# Main.net
KiCad netlist of a schematic drawn in EAGLE
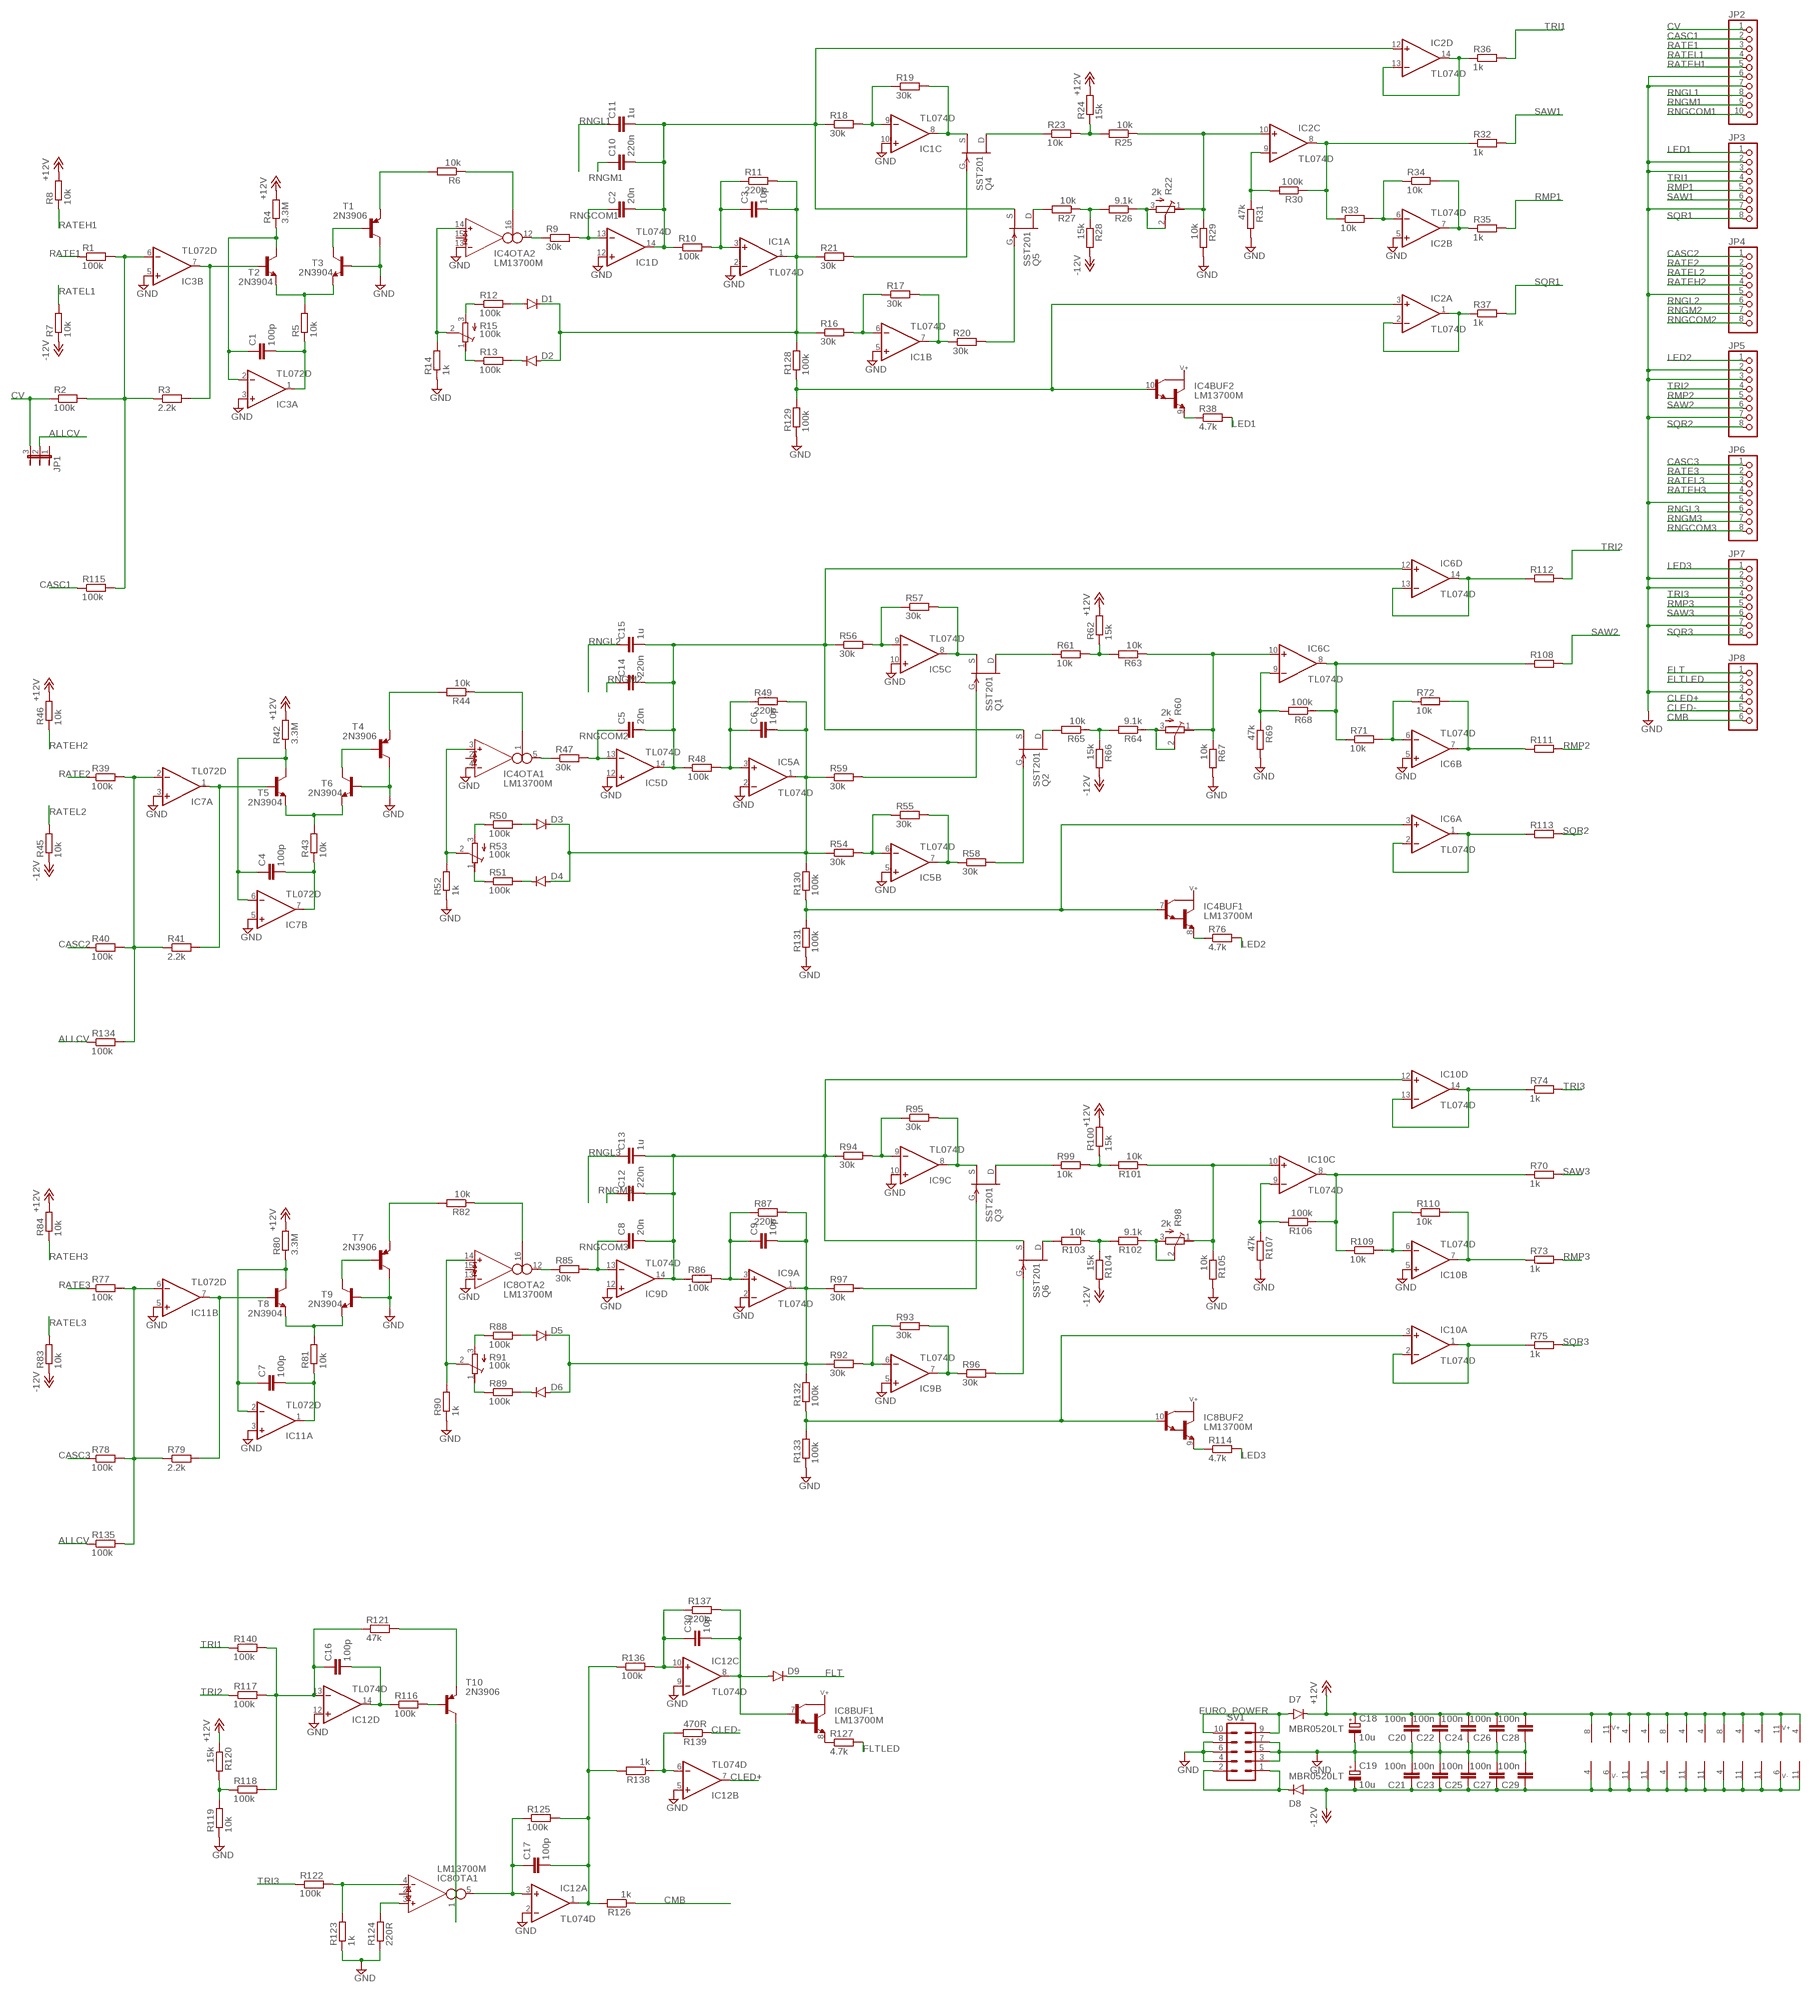
[diagram p0: schematic, sheet 1]

(export (version "E")
  (design (tool "Eeschema 10.0.6"))
  (components
    (comp (ref "C1")
      (value "100p")
      (footprint "eagle-import:C0805")
      (libsource (lib "eagle-import") (part "C-EUC0805"))
    )
    (comp (ref "C2")
      (value "20n")
      (footprint "eagle-import:C050-025X075")
      (libsource (lib "eagle-import") (part "C-EU050-025X075"))
    )
    (comp (ref "C3")
      (value "10p")
      (footprint "eagle-import:C0805")
      (libsource (lib "eagle-import") (part "C-EUC0805"))
    )
    (comp (ref "C4")
      (value "100p")
      (footprint "eagle-import:C0805")
      (libsource (lib "eagle-import") (part "C-EUC0805"))
    )
    (comp (ref "C5")
      (value "20n")
      (footprint "eagle-import:C050-025X075")
      (libsource (lib "eagle-import") (part "C-EU050-025X075"))
    )
    (comp (ref "C6")
      (value "10p")
      (footprint "eagle-import:C0805")
      (libsource (lib "eagle-import") (part "C-EUC0805"))
    )
    (comp (ref "C7")
      (value "100p")
      (footprint "eagle-import:C0805")
      (libsource (lib "eagle-import") (part "C-EUC0805"))
    )
    (comp (ref "C8")
      (value "20n")
      (footprint "eagle-import:C050-025X075")
      (libsource (lib "eagle-import") (part "C-EU050-025X075"))
    )
    (comp (ref "C9")
      (value "10p")
      (footprint "eagle-import:C0805")
      (libsource (lib "eagle-import") (part "C-EUC0805"))
    )
    (comp (ref "C10")
      (value "220n")
      (footprint "eagle-import:C050-035X075")
      (libsource (lib "eagle-import") (part "C-EU050-035X075"))
    )
    (comp (ref "C11")
      (value "1u")
      (footprint "eagle-import:C050-045X075")
      (libsource (lib "eagle-import") (part "C-EU050-045X075"))
    )
    (comp (ref "C12")
      (value "220n")
      (footprint "eagle-import:C050-035X075")
      (libsource (lib "eagle-import") (part "C-EU050-035X075"))
    )
    (comp (ref "C13")
      (value "1u")
      (footprint "eagle-import:C050-045X075")
      (libsource (lib "eagle-import") (part "C-EU050-045X075"))
    )
    (comp (ref "C14")
      (value "220n")
      (footprint "eagle-import:C050-035X075")
      (libsource (lib "eagle-import") (part "C-EU050-035X075"))
    )
    (comp (ref "C15")
      (value "1u")
      (footprint "eagle-import:C050-045X075")
      (libsource (lib "eagle-import") (part "C-EU050-045X075"))
    )
    (comp (ref "C16")
      (value "100p")
      (footprint "eagle-import:C0805")
      (libsource (lib "eagle-import") (part "C-EUC0805"))
    )
    (comp (ref "C17")
      (value "100p")
      (footprint "eagle-import:C0805")
      (libsource (lib "eagle-import") (part "C-EUC0805"))
    )
    (comp (ref "C18")
      (value "10u")
      (footprint "eagle-import:E2,5-5")
      (libsource (lib "eagle-import") (part "CPOL-EUE2.5-5"))
    )
    (comp (ref "C19")
      (value "10u")
      (footprint "eagle-import:E2,5-5")
      (libsource (lib "eagle-import") (part "CPOL-EUE2.5-5"))
    )
    (comp (ref "C20")
      (value "100n")
      (footprint "eagle-import:C0805")
      (libsource (lib "eagle-import") (part "C-EUC0805"))
    )
    (comp (ref "C21")
      (value "100n")
      (footprint "eagle-import:C0805")
      (libsource (lib "eagle-import") (part "C-EUC0805"))
    )
    (comp (ref "C22")
      (value "100n")
      (footprint "eagle-import:C0805")
      (libsource (lib "eagle-import") (part "C-EUC0805"))
    )
    (comp (ref "C23")
      (value "100n")
      (footprint "eagle-import:C0805")
      (libsource (lib "eagle-import") (part "C-EUC0805"))
    )
    (comp (ref "C24")
      (value "100n")
      (footprint "eagle-import:C0805")
      (libsource (lib "eagle-import") (part "C-EUC0805"))
    )
    (comp (ref "C25")
      (value "100n")
      (footprint "eagle-import:C0805")
      (libsource (lib "eagle-import") (part "C-EUC0805"))
    )
    (comp (ref "C26")
      (value "100n")
      (footprint "eagle-import:C0805")
      (libsource (lib "eagle-import") (part "C-EUC0805"))
    )
    (comp (ref "C27")
      (value "100n")
      (footprint "eagle-import:C0805")
      (libsource (lib "eagle-import") (part "C-EUC0805"))
    )
    (comp (ref "C28")
      (value "100n")
      (footprint "eagle-import:C0805")
      (libsource (lib "eagle-import") (part "C-EUC0805"))
    )
    (comp (ref "C29")
      (value "100n")
      (footprint "eagle-import:C0805")
      (libsource (lib "eagle-import") (part "C-EUC0805"))
    )
    (comp (ref "C30")
      (value "10p")
      (footprint "eagle-import:C0805")
      (libsource (lib "eagle-import") (part "C-EUC0805"))
    )
    (comp (ref "D1")
      (value "DIODE-SOD123")
      (footprint "eagle-import:SOD123")
      (libsource (lib "eagle-import") (part "DIODE-SOD123"))
    )
    (comp (ref "D2")
      (value "DIODE-SOD123")
      (footprint "eagle-import:SOD123")
      (libsource (lib "eagle-import") (part "DIODE-SOD123"))
    )
    (comp (ref "D3")
      (value "DIODE-SOD123")
      (footprint "eagle-import:SOD123")
      (libsource (lib "eagle-import") (part "DIODE-SOD123"))
    )
    (comp (ref "D4")
      (value "DIODE-SOD123")
      (footprint "eagle-import:SOD123")
      (libsource (lib "eagle-import") (part "DIODE-SOD123"))
    )
    (comp (ref "D5")
      (value "DIODE-SOD123")
      (footprint "eagle-import:SOD123")
      (libsource (lib "eagle-import") (part "DIODE-SOD123"))
    )
    (comp (ref "D6")
      (value "DIODE-SOD123")
      (footprint "eagle-import:SOD123")
      (libsource (lib "eagle-import") (part "DIODE-SOD123"))
    )
    (comp (ref "D7")
      (value "MBR0520LT")
      (footprint "eagle-import:SOD123")
      (libsource (lib "eagle-import") (part "MBR0520LT"))
    )
    (comp (ref "D8")
      (value "MBR0520LT")
      (footprint "eagle-import:SOD123")
      (libsource (lib "eagle-import") (part "MBR0520LT"))
    )
    (comp (ref "D9")
      (value "DIODE-SOD123")
      (footprint "eagle-import:SOD123")
      (libsource (lib "eagle-import") (part "DIODE-SOD123"))
    )
    (comp (ref "IC1")
      (value "TL074D")
      (footprint "eagle-import:SO14")
      (libsource (lib "eagle-import") (part "TL074D"))
    )
    (comp (ref "IC2")
      (value "TL074D")
      (footprint "eagle-import:SO14")
      (libsource (lib "eagle-import") (part "TL074D"))
    )
    (comp (ref "IC3")
      (value "TL072D")
      (footprint "eagle-import:SO08")
      (libsource (lib "eagle-import") (part "TL072D"))
    )
    (comp (ref "IC4")
      (value "LM13700M")
      (footprint "eagle-import:SO16")
      (libsource (lib "eagle-import") (part "LM13700M"))
    )
    (comp (ref "IC5")
      (value "TL074D")
      (footprint "eagle-import:SO14")
      (libsource (lib "eagle-import") (part "TL074D"))
    )
    (comp (ref "IC6")
      (value "TL074D")
      (footprint "eagle-import:SO14")
      (libsource (lib "eagle-import") (part "TL074D"))
    )
    (comp (ref "IC7")
      (value "TL072D")
      (footprint "eagle-import:SO08")
      (libsource (lib "eagle-import") (part "TL072D"))
    )
    (comp (ref "IC8")
      (value "LM13700M")
      (footprint "eagle-import:SO16")
      (libsource (lib "eagle-import") (part "LM13700M"))
    )
    (comp (ref "IC9")
      (value "TL074D")
      (footprint "eagle-import:SO14")
      (libsource (lib "eagle-import") (part "TL074D"))
    )
    (comp (ref "IC10")
      (value "TL074D")
      (footprint "eagle-import:SO14")
      (libsource (lib "eagle-import") (part "TL074D"))
    )
    (comp (ref "IC11")
      (value "TL072D")
      (footprint "eagle-import:SO08")
      (libsource (lib "eagle-import") (part "TL072D"))
    )
    (comp (ref "IC12")
      (value "TL074D")
      (footprint "eagle-import:SO14")
      (libsource (lib "eagle-import") (part "TL074D"))
    )
    (comp (ref "JP1")
      (value "JP2E")
      (footprint "eagle-import:JP2")
      (libsource (lib "eagle-import") (part "JP2E"))
    )
    (comp (ref "JP2")
      (value "PINHD-1X10")
      (footprint "eagle-import:1X10")
      (libsource (lib "eagle-import") (part "PINHD-1X10"))
    )
    (comp (ref "JP3")
      (value "PINHD-1X8")
      (footprint "eagle-import:1X08")
      (libsource (lib "eagle-import") (part "PINHD-1X8"))
    )
    (comp (ref "JP4")
      (value "PINHD-1X8")
      (footprint "eagle-import:1X08")
      (libsource (lib "eagle-import") (part "PINHD-1X8"))
    )
    (comp (ref "JP5")
      (value "PINHD-1X8")
      (footprint "eagle-import:1X08")
      (libsource (lib "eagle-import") (part "PINHD-1X8"))
    )
    (comp (ref "JP6")
      (value "PINHD-1X8")
      (footprint "eagle-import:1X08")
      (libsource (lib "eagle-import") (part "PINHD-1X8"))
    )
    (comp (ref "JP7")
      (value "PINHD-1X8")
      (footprint "eagle-import:1X08")
      (libsource (lib "eagle-import") (part "PINHD-1X8"))
    )
    (comp (ref "JP8")
      (value "PINHD-1X6")
      (footprint "eagle-import:1X06")
      (libsource (lib "eagle-import") (part "PINHD-1X6"))
    )
    (comp (ref "Q1")
      (value "SST201")
      (footprint "eagle-import:SOT23")
      (libsource (lib "eagle-import") (part "?20SST1"))
    )
    (comp (ref "Q2")
      (value "SST201")
      (footprint "eagle-import:SOT23")
      (libsource (lib "eagle-import") (part "?20SST1"))
    )
    (comp (ref "Q3")
      (value "SST201")
      (footprint "eagle-import:SOT23")
      (libsource (lib "eagle-import") (part "?20SST1"))
    )
    (comp (ref "Q4")
      (value "SST201")
      (footprint "eagle-import:SOT23")
      (libsource (lib "eagle-import") (part "?20SST1"))
    )
    (comp (ref "Q5")
      (value "SST201")
      (footprint "eagle-import:SOT23")
      (libsource (lib "eagle-import") (part "?20SST1"))
    )
    (comp (ref "Q6")
      (value "SST201")
      (footprint "eagle-import:SOT23")
      (libsource (lib "eagle-import") (part "?20SST1"))
    )
    (comp (ref "R1")
      (value "100k")
      (footprint "eagle-import:R0805")
      (libsource (lib "eagle-import") (part "R-EU_R0805"))
    )
    (comp (ref "R2")
      (value "100k")
      (footprint "eagle-import:R0805")
      (libsource (lib "eagle-import") (part "R-EU_R0805"))
    )
    (comp (ref "R3")
      (value "2.2k")
      (footprint "eagle-import:R0805")
      (libsource (lib "eagle-import") (part "R-EU_R0805"))
    )
    (comp (ref "R4")
      (value "3.3M")
      (footprint "eagle-import:R0805")
      (libsource (lib "eagle-import") (part "R-EU_R0805"))
    )
    (comp (ref "R5")
      (value "10k")
      (footprint "eagle-import:R0805")
      (libsource (lib "eagle-import") (part "R-EU_R0805"))
    )
    (comp (ref "R6")
      (value "10k")
      (footprint "eagle-import:R0805")
      (libsource (lib "eagle-import") (part "R-EU_R0805"))
    )
    (comp (ref "R7")
      (value "10k")
      (footprint "eagle-import:R0805")
      (libsource (lib "eagle-import") (part "R-EU_R0805"))
    )
    (comp (ref "R8")
      (value "10k")
      (footprint "eagle-import:R0805")
      (libsource (lib "eagle-import") (part "R-EU_R0805"))
    )
    (comp (ref "R9")
      (value "30k")
      (footprint "eagle-import:R0805")
      (libsource (lib "eagle-import") (part "R-EU_R0805"))
    )
    (comp (ref "R10")
      (value "100k")
      (footprint "eagle-import:R0805")
      (libsource (lib "eagle-import") (part "R-EU_R0805"))
    )
    (comp (ref "R11")
      (value "220k")
      (footprint "eagle-import:R0805")
      (libsource (lib "eagle-import") (part "R-EU_R0805"))
    )
    (comp (ref "R12")
      (value "100k")
      (footprint "eagle-import:R0805")
      (libsource (lib "eagle-import") (part "R-EU_R0805"))
    )
    (comp (ref "R13")
      (value "100k")
      (footprint "eagle-import:R0805")
      (libsource (lib "eagle-import") (part "R-EU_R0805"))
    )
    (comp (ref "R14")
      (value "1k")
      (footprint "eagle-import:R0805")
      (libsource (lib "eagle-import") (part "R-EU_R0805"))
    )
    (comp (ref "R15")
      (value "100k")
      (footprint "eagle-import:RTRIMT93XB")
      (libsource (lib "eagle-import") (part "R-TRIMMT93XB"))
    )
    (comp (ref "R16")
      (value "30k")
      (footprint "eagle-import:R0805")
      (libsource (lib "eagle-import") (part "R-EU_R0805"))
    )
    (comp (ref "R17")
      (value "30k")
      (footprint "eagle-import:R0805")
      (libsource (lib "eagle-import") (part "R-EU_R0805"))
    )
    (comp (ref "R18")
      (value "30k")
      (footprint "eagle-import:R0805")
      (libsource (lib "eagle-import") (part "R-EU_R0805"))
    )
    (comp (ref "R19")
      (value "30k")
      (footprint "eagle-import:R0805")
      (libsource (lib "eagle-import") (part "R-EU_R0805"))
    )
    (comp (ref "R20")
      (value "30k")
      (footprint "eagle-import:R0805")
      (libsource (lib "eagle-import") (part "R-EU_R0805"))
    )
    (comp (ref "R21")
      (value "30k")
      (footprint "eagle-import:R0805")
      (libsource (lib "eagle-import") (part "R-EU_R0805"))
    )
    (comp (ref "R22")
      (value "2k")
      (footprint "eagle-import:RTRIMT93XB")
      (libsource (lib "eagle-import") (part "R-TRIMMT93XB"))
    )
    (comp (ref "R23")
      (value "10k")
      (footprint "eagle-import:R0805")
      (libsource (lib "eagle-import") (part "R-EU_R0805"))
    )
    (comp (ref "R24")
      (value "15k")
      (footprint "eagle-import:R0805")
      (libsource (lib "eagle-import") (part "R-EU_R0805"))
    )
    (comp (ref "R25")
      (value "10k")
      (footprint "eagle-import:R0805")
      (libsource (lib "eagle-import") (part "R-EU_R0805"))
    )
    (comp (ref "R26")
      (value "9.1k")
      (footprint "eagle-import:R0805")
      (libsource (lib "eagle-import") (part "R-EU_R0805"))
    )
    (comp (ref "R27")
      (value "10k")
      (footprint "eagle-import:R0805")
      (libsource (lib "eagle-import") (part "R-EU_R0805"))
    )
    (comp (ref "R28")
      (value "15k")
      (footprint "eagle-import:R0805")
      (libsource (lib "eagle-import") (part "R-EU_R0805"))
    )
    (comp (ref "R29")
      (value "10k")
      (footprint "eagle-import:R0805")
      (libsource (lib "eagle-import") (part "R-EU_R0805"))
    )
    (comp (ref "R30")
      (value "100k")
      (footprint "eagle-import:R0805")
      (libsource (lib "eagle-import") (part "R-EU_R0805"))
    )
    (comp (ref "R31")
      (value "47k")
      (footprint "eagle-import:R0805")
      (libsource (lib "eagle-import") (part "R-EU_R0805"))
    )
    (comp (ref "R32")
      (value "1k")
      (footprint "eagle-import:R0805")
      (libsource (lib "eagle-import") (part "R-EU_R0805"))
    )
    (comp (ref "R33")
      (value "10k")
      (footprint "eagle-import:R0805")
      (libsource (lib "eagle-import") (part "R-EU_R0805"))
    )
    (comp (ref "R34")
      (value "10k")
      (footprint "eagle-import:R0805")
      (libsource (lib "eagle-import") (part "R-EU_R0805"))
    )
    (comp (ref "R35")
      (value "1k")
      (footprint "eagle-import:R0805")
      (libsource (lib "eagle-import") (part "R-EU_R0805"))
    )
    (comp (ref "R36")
      (value "1k")
      (footprint "eagle-import:R0805")
      (libsource (lib "eagle-import") (part "R-EU_R0805"))
    )
    (comp (ref "R37")
      (value "1k")
      (footprint "eagle-import:R0805")
      (libsource (lib "eagle-import") (part "R-EU_R0805"))
    )
    (comp (ref "R38")
      (value "4.7k")
      (footprint "eagle-import:R0805")
      (libsource (lib "eagle-import") (part "R-EU_R0805"))
    )
    (comp (ref "R39")
      (value "100k")
      (footprint "eagle-import:R0805")
      (libsource (lib "eagle-import") (part "R-EU_R0805"))
    )
    (comp (ref "R40")
      (value "100k")
      (footprint "eagle-import:R0805")
      (libsource (lib "eagle-import") (part "R-EU_R0805"))
    )
    (comp (ref "R41")
      (value "2.2k")
      (footprint "eagle-import:R0805")
      (libsource (lib "eagle-import") (part "R-EU_R0805"))
    )
    (comp (ref "R42")
      (value "3.3M")
      (footprint "eagle-import:R0805")
      (libsource (lib "eagle-import") (part "R-EU_R0805"))
    )
    (comp (ref "R43")
      (value "10k")
      (footprint "eagle-import:R0805")
      (libsource (lib "eagle-import") (part "R-EU_R0805"))
    )
    (comp (ref "R44")
      (value "10k")
      (footprint "eagle-import:R0805")
      (libsource (lib "eagle-import") (part "R-EU_R0805"))
    )
    (comp (ref "R45")
      (value "10k")
      (footprint "eagle-import:R0805")
      (libsource (lib "eagle-import") (part "R-EU_R0805"))
    )
    (comp (ref "R46")
      (value "10k")
      (footprint "eagle-import:R0805")
      (libsource (lib "eagle-import") (part "R-EU_R0805"))
    )
    (comp (ref "R47")
      (value "30k")
      (footprint "eagle-import:R0805")
      (libsource (lib "eagle-import") (part "R-EU_R0805"))
    )
    (comp (ref "R48")
      (value "100k")
      (footprint "eagle-import:R0805")
      (libsource (lib "eagle-import") (part "R-EU_R0805"))
    )
    (comp (ref "R49")
      (value "220k")
      (footprint "eagle-import:R0805")
      (libsource (lib "eagle-import") (part "R-EU_R0805"))
    )
    (comp (ref "R50")
      (value "100k")
      (footprint "eagle-import:R0805")
      (libsource (lib "eagle-import") (part "R-EU_R0805"))
    )
    (comp (ref "R51")
      (value "100k")
      (footprint "eagle-import:R0805")
      (libsource (lib "eagle-import") (part "R-EU_R0805"))
    )
    (comp (ref "R52")
      (value "1k")
      (footprint "eagle-import:R0805")
      (libsource (lib "eagle-import") (part "R-EU_R0805"))
    )
    (comp (ref "R53")
      (value "100k")
      (footprint "eagle-import:RTRIMT93XB")
      (libsource (lib "eagle-import") (part "R-TRIMMT93XB"))
    )
    (comp (ref "R54")
      (value "30k")
      (footprint "eagle-import:R0805")
      (libsource (lib "eagle-import") (part "R-EU_R0805"))
    )
    (comp (ref "R55")
      (value "30k")
      (footprint "eagle-import:R0805")
      (libsource (lib "eagle-import") (part "R-EU_R0805"))
    )
    (comp (ref "R56")
      (value "30k")
      (footprint "eagle-import:R0805")
      (libsource (lib "eagle-import") (part "R-EU_R0805"))
    )
    (comp (ref "R57")
      (value "30k")
      (footprint "eagle-import:R0805")
      (libsource (lib "eagle-import") (part "R-EU_R0805"))
    )
    (comp (ref "R58")
      (value "30k")
      (footprint "eagle-import:R0805")
      (libsource (lib "eagle-import") (part "R-EU_R0805"))
    )
    (comp (ref "R59")
      (value "30k")
      (footprint "eagle-import:R0805")
      (libsource (lib "eagle-import") (part "R-EU_R0805"))
    )
    (comp (ref "R60")
      (value "2k")
      (footprint "eagle-import:RTRIMT93XB")
      (libsource (lib "eagle-import") (part "R-TRIMMT93XB"))
    )
    (comp (ref "R61")
      (value "10k")
      (footprint "eagle-import:R0805")
      (libsource (lib "eagle-import") (part "R-EU_R0805"))
    )
    (comp (ref "R62")
      (value "15k")
      (footprint "eagle-import:R0805")
      (libsource (lib "eagle-import") (part "R-EU_R0805"))
    )
    (comp (ref "R63")
      (value "10k")
      (footprint "eagle-import:R0805")
      (libsource (lib "eagle-import") (part "R-EU_R0805"))
    )
    (comp (ref "R64")
      (value "9.1k")
      (footprint "eagle-import:R0805")
      (libsource (lib "eagle-import") (part "R-EU_R0805"))
    )
    (comp (ref "R65")
      (value "10k")
      (footprint "eagle-import:R0805")
      (libsource (lib "eagle-import") (part "R-EU_R0805"))
    )
    (comp (ref "R66")
      (value "15k")
      (footprint "eagle-import:R0805")
      (libsource (lib "eagle-import") (part "R-EU_R0805"))
    )
    (comp (ref "R67")
      (value "10k")
      (footprint "eagle-import:R0805")
      (libsource (lib "eagle-import") (part "R-EU_R0805"))
    )
    (comp (ref "R68")
      (value "100k")
      (footprint "eagle-import:R0805")
      (libsource (lib "eagle-import") (part "R-EU_R0805"))
    )
    (comp (ref "R69")
      (value "47k")
      (footprint "eagle-import:R0805")
      (libsource (lib "eagle-import") (part "R-EU_R0805"))
    )
    (comp (ref "R70")
      (value "1k")
      (footprint "eagle-import:R0805")
      (libsource (lib "eagle-import") (part "R-EU_R0805"))
    )
    (comp (ref "R71")
      (value "10k")
      (footprint "eagle-import:R0805")
      (libsource (lib "eagle-import") (part "R-EU_R0805"))
    )
    (comp (ref "R72")
      (value "10k")
      (footprint "eagle-import:R0805")
      (libsource (lib "eagle-import") (part "R-EU_R0805"))
    )
    (comp (ref "R73")
      (value "1k")
      (footprint "eagle-import:R0805")
      (libsource (lib "eagle-import") (part "R-EU_R0805"))
    )
    (comp (ref "R74")
      (value "1k")
      (footprint "eagle-import:R0805")
      (libsource (lib "eagle-import") (part "R-EU_R0805"))
    )
    (comp (ref "R75")
      (value "1k")
      (footprint "eagle-import:R0805")
      (libsource (lib "eagle-import") (part "R-EU_R0805"))
    )
    (comp (ref "R76")
      (value "4.7k")
      (footprint "eagle-import:R0805")
      (libsource (lib "eagle-import") (part "R-EU_R0805"))
    )
    (comp (ref "R77")
      (value "100k")
      (footprint "eagle-import:R0805")
      (libsource (lib "eagle-import") (part "R-EU_R0805"))
    )
    (comp (ref "R78")
      (value "100k")
      (footprint "eagle-import:R0805")
      (libsource (lib "eagle-import") (part "R-EU_R0805"))
    )
    (comp (ref "R79")
      (value "2.2k")
      (footprint "eagle-import:R0805")
      (libsource (lib "eagle-import") (part "R-EU_R0805"))
    )
    (comp (ref "R80")
      (value "3.3M")
      (footprint "eagle-import:R0805")
      (libsource (lib "eagle-import") (part "R-EU_R0805"))
    )
    (comp (ref "R81")
      (value "10k")
      (footprint "eagle-import:R0805")
      (libsource (lib "eagle-import") (part "R-EU_R0805"))
    )
    (comp (ref "R82")
      (value "10k")
      (footprint "eagle-import:R0805")
      (libsource (lib "eagle-import") (part "R-EU_R0805"))
    )
    (comp (ref "R83")
      (value "10k")
      (footprint "eagle-import:R0805")
      (libsource (lib "eagle-import") (part "R-EU_R0805"))
    )
    (comp (ref "R84")
      (value "10k")
      (footprint "eagle-import:R0805")
      (libsource (lib "eagle-import") (part "R-EU_R0805"))
    )
    (comp (ref "R85")
      (value "30k")
      (footprint "eagle-import:R0805")
      (libsource (lib "eagle-import") (part "R-EU_R0805"))
    )
    (comp (ref "R86")
      (value "100k")
      (footprint "eagle-import:R0805")
      (libsource (lib "eagle-import") (part "R-EU_R0805"))
    )
    (comp (ref "R87")
      (value "220k")
      (footprint "eagle-import:R0805")
      (libsource (lib "eagle-import") (part "R-EU_R0805"))
    )
    (comp (ref "R88")
      (value "100k")
      (footprint "eagle-import:R0805")
      (libsource (lib "eagle-import") (part "R-EU_R0805"))
    )
    (comp (ref "R89")
      (value "100k")
      (footprint "eagle-import:R0805")
      (libsource (lib "eagle-import") (part "R-EU_R0805"))
    )
    (comp (ref "R90")
      (value "1k")
      (footprint "eagle-import:R0805")
      (libsource (lib "eagle-import") (part "R-EU_R0805"))
    )
    (comp (ref "R91")
      (value "100k")
      (footprint "eagle-import:RTRIMT93XB")
      (libsource (lib "eagle-import") (part "R-TRIMMT93XB"))
    )
    (comp (ref "R92")
      (value "30k")
      (footprint "eagle-import:R0805")
      (libsource (lib "eagle-import") (part "R-EU_R0805"))
    )
    (comp (ref "R93")
      (value "30k")
      (footprint "eagle-import:R0805")
      (libsource (lib "eagle-import") (part "R-EU_R0805"))
    )
    (comp (ref "R94")
      (value "30k")
      (footprint "eagle-import:R0805")
      (libsource (lib "eagle-import") (part "R-EU_R0805"))
    )
    (comp (ref "R95")
      (value "30k")
      (footprint "eagle-import:R0805")
      (libsource (lib "eagle-import") (part "R-EU_R0805"))
    )
    (comp (ref "R96")
      (value "30k")
      (footprint "eagle-import:R0805")
      (libsource (lib "eagle-import") (part "R-EU_R0805"))
    )
    (comp (ref "R97")
      (value "30k")
      (footprint "eagle-import:R0805")
      (libsource (lib "eagle-import") (part "R-EU_R0805"))
    )
    (comp (ref "R98")
      (value "2k")
      (footprint "eagle-import:RTRIMT93XB")
      (libsource (lib "eagle-import") (part "R-TRIMMT93XB"))
    )
    (comp (ref "R99")
      (value "10k")
      (footprint "eagle-import:R0805")
      (libsource (lib "eagle-import") (part "R-EU_R0805"))
    )
    (comp (ref "R100")
      (value "15k")
      (footprint "eagle-import:R0805")
      (libsource (lib "eagle-import") (part "R-EU_R0805"))
    )
    (comp (ref "R101")
      (value "10k")
      (footprint "eagle-import:R0805")
      (libsource (lib "eagle-import") (part "R-EU_R0805"))
    )
    (comp (ref "R102")
      (value "9.1k")
      (footprint "eagle-import:R0805")
      (libsource (lib "eagle-import") (part "R-EU_R0805"))
    )
    (comp (ref "R103")
      (value "10k")
      (footprint "eagle-import:R0805")
      (libsource (lib "eagle-import") (part "R-EU_R0805"))
    )
    (comp (ref "R104")
      (value "15k")
      (footprint "eagle-import:R0805")
      (libsource (lib "eagle-import") (part "R-EU_R0805"))
    )
    (comp (ref "R105")
      (value "10k")
      (footprint "eagle-import:R0805")
      (libsource (lib "eagle-import") (part "R-EU_R0805"))
    )
    (comp (ref "R106")
      (value "100k")
      (footprint "eagle-import:R0805")
      (libsource (lib "eagle-import") (part "R-EU_R0805"))
    )
    (comp (ref "R107")
      (value "47k")
      (footprint "eagle-import:R0805")
      (libsource (lib "eagle-import") (part "R-EU_R0805"))
    )
    (comp (ref "R108")
      (value "R-EU_R0805")
      (footprint "eagle-import:R0805")
      (libsource (lib "eagle-import") (part "R-EU_R0805"))
    )
    (comp (ref "R109")
      (value "10k")
      (footprint "eagle-import:R0805")
      (libsource (lib "eagle-import") (part "R-EU_R0805"))
    )
    (comp (ref "R110")
      (value "10k")
      (footprint "eagle-import:R0805")
      (libsource (lib "eagle-import") (part "R-EU_R0805"))
    )
    (comp (ref "R111")
      (value "R-EU_R0805")
      (footprint "eagle-import:R0805")
      (libsource (lib "eagle-import") (part "R-EU_R0805"))
    )
    (comp (ref "R112")
      (value "R-EU_R0805")
      (footprint "eagle-import:R0805")
      (libsource (lib "eagle-import") (part "R-EU_R0805"))
    )
    (comp (ref "R113")
      (value "R-EU_R0805")
      (footprint "eagle-import:R0805")
      (libsource (lib "eagle-import") (part "R-EU_R0805"))
    )
    (comp (ref "R114")
      (value "4.7k")
      (footprint "eagle-import:R0805")
      (libsource (lib "eagle-import") (part "R-EU_R0805"))
    )
    (comp (ref "R115")
      (value "100k")
      (footprint "eagle-import:R0805")
      (libsource (lib "eagle-import") (part "R-EU_R0805"))
    )
    (comp (ref "R116")
      (value "100k")
      (footprint "eagle-import:R0805")
      (libsource (lib "eagle-import") (part "R-EU_R0805"))
    )
    (comp (ref "R117")
      (value "100k")
      (footprint "eagle-import:R0805")
      (libsource (lib "eagle-import") (part "R-EU_R0805"))
    )
    (comp (ref "R118")
      (value "100k")
      (footprint "eagle-import:R0805")
      (libsource (lib "eagle-import") (part "R-EU_R0805"))
    )
    (comp (ref "R119")
      (value "10k")
      (footprint "eagle-import:R0805")
      (libsource (lib "eagle-import") (part "R-EU_R0805"))
    )
    (comp (ref "R120")
      (value "15k")
      (footprint "eagle-import:R0805")
      (libsource (lib "eagle-import") (part "R-EU_R0805"))
    )
    (comp (ref "R121")
      (value "47k")
      (footprint "eagle-import:R0805")
      (libsource (lib "eagle-import") (part "R-EU_R0805"))
    )
    (comp (ref "R122")
      (value "100k")
      (footprint "eagle-import:R0805")
      (libsource (lib "eagle-import") (part "R-EU_R0805"))
    )
    (comp (ref "R123")
      (value "1k")
      (footprint "eagle-import:R0805")
      (libsource (lib "eagle-import") (part "R-EU_R0805"))
    )
    (comp (ref "R124")
      (value "220R")
      (footprint "eagle-import:R0805")
      (libsource (lib "eagle-import") (part "R-EU_R0805"))
    )
    (comp (ref "R125")
      (value "100k")
      (footprint "eagle-import:R0805")
      (libsource (lib "eagle-import") (part "R-EU_R0805"))
    )
    (comp (ref "R126")
      (value "1k")
      (footprint "eagle-import:R0805")
      (libsource (lib "eagle-import") (part "R-EU_R0805"))
    )
    (comp (ref "R127")
      (value "4.7k")
      (footprint "eagle-import:R0805")
      (libsource (lib "eagle-import") (part "R-EU_R0805"))
    )
    (comp (ref "R128")
      (value "100k")
      (footprint "eagle-import:R0805")
      (libsource (lib "eagle-import") (part "R-EU_R0805"))
    )
    (comp (ref "R129")
      (value "100k")
      (footprint "eagle-import:R0805")
      (libsource (lib "eagle-import") (part "R-EU_R0805"))
    )
    (comp (ref "R130")
      (value "100k")
      (footprint "eagle-import:R0805")
      (libsource (lib "eagle-import") (part "R-EU_R0805"))
    )
    (comp (ref "R131")
      (value "100k")
      (footprint "eagle-import:R0805")
      (libsource (lib "eagle-import") (part "R-EU_R0805"))
    )
    (comp (ref "R132")
      (value "100k")
      (footprint "eagle-import:R0805")
      (libsource (lib "eagle-import") (part "R-EU_R0805"))
    )
    (comp (ref "R133")
      (value "100k")
      (footprint "eagle-import:R0805")
      (libsource (lib "eagle-import") (part "R-EU_R0805"))
    )
    (comp (ref "R134")
      (value "100k")
      (footprint "eagle-import:R0805")
      (libsource (lib "eagle-import") (part "R-EU_R0805"))
    )
    (comp (ref "R135")
      (value "100k")
      (footprint "eagle-import:R0805")
      (libsource (lib "eagle-import") (part "R-EU_R0805"))
    )
    (comp (ref "R136")
      (value "100k")
      (footprint "eagle-import:R0805")
      (libsource (lib "eagle-import") (part "R-EU_R0805"))
    )
    (comp (ref "R137")
      (value "220k")
      (footprint "eagle-import:R0805")
      (libsource (lib "eagle-import") (part "R-EU_R0805"))
    )
    (comp (ref "R138")
      (value "1k")
      (footprint "eagle-import:R0805")
      (libsource (lib "eagle-import") (part "R-EU_R0805"))
    )
    (comp (ref "R139")
      (value "470R")
      (footprint "eagle-import:R0805")
      (libsource (lib "eagle-import") (part "R-EU_R0805"))
    )
    (comp (ref "R140")
      (value "100k")
      (footprint "eagle-import:R0805")
      (libsource (lib "eagle-import") (part "R-EU_R0805"))
    )
    (comp (ref "SV1")
      (value "EURO_POWER")
      (footprint "eagle-import:EURO_PWR_HEADER_FAT")
      (libsource (lib "eagle-import") (part "EURO_POWER_HEADERFAT_PADS"))
    )
    (comp (ref "T1")
      (value "2N3906")
      (footprint "eagle-import:SOT23-BEC")
      (libsource (lib "eagle-import") (part "-PNP-SOT23-BECMMBT3906LT1"))
    )
    (comp (ref "T2")
      (value "2N3904")
      (footprint "eagle-import:SOT23-BEC")
      (libsource (lib "eagle-import") (part "-NPN-SOT23-BECMMBT3904LT1"))
    )
    (comp (ref "T3")
      (value "2N3904")
      (footprint "eagle-import:SOT23-BEC")
      (libsource (lib "eagle-import") (part "-NPN-SOT23-BECMMBT3904LT1"))
    )
    (comp (ref "T4")
      (value "2N3906")
      (footprint "eagle-import:SOT23-BEC")
      (libsource (lib "eagle-import") (part "-PNP-SOT23-BECMMBT3906LT1"))
    )
    (comp (ref "T5")
      (value "2N3904")
      (footprint "eagle-import:SOT23-BEC")
      (libsource (lib "eagle-import") (part "-NPN-SOT23-BECMMBT3904LT1"))
    )
    (comp (ref "T6")
      (value "2N3904")
      (footprint "eagle-import:SOT23-BEC")
      (libsource (lib "eagle-import") (part "-NPN-SOT23-BECMMBT3904LT1"))
    )
    (comp (ref "T7")
      (value "2N3906")
      (footprint "eagle-import:SOT23-BEC")
      (libsource (lib "eagle-import") (part "-PNP-SOT23-BECMMBT3906LT1"))
    )
    (comp (ref "T8")
      (value "2N3904")
      (footprint "eagle-import:SOT23-BEC")
      (libsource (lib "eagle-import") (part "-NPN-SOT23-BECMMBT3904LT1"))
    )
    (comp (ref "T9")
      (value "2N3904")
      (footprint "eagle-import:SOT23-BEC")
      (libsource (lib "eagle-import") (part "-NPN-SOT23-BECMMBT3904LT1"))
    )
    (comp (ref "T10")
      (value "2N3906")
      (footprint "eagle-import:SOT23-BEC")
      (libsource (lib "eagle-import") (part "-PNP-SOT23-BECMMBT3906LT1"))
    )
  )
  (nets
    (net (code "1") (name "+12V") (class "Default")
      (node (ref "C18") (pin "+") (pinfunction "+_+") (pintype "passive"))
      (node (ref "C20") (pin "2") (pinfunction "2_2") (pintype "passive"))
      (node (ref "C22") (pin "2") (pinfunction "2_2") (pintype "passive"))
      (node (ref "C24") (pin "2") (pinfunction "2_2") (pintype "passive"))
      (node (ref "C26") (pin "2") (pinfunction "2_2") (pintype "passive"))
      (node (ref "C28") (pin "2") (pinfunction "2_2") (pintype "passive"))
      (node (ref "D7") (pin "C") (pinfunction "C_C") (pintype "passive"))
      (node (ref "IC1") (pin "4") (pinfunction "V+_4") (pintype "power_in"))
      (node (ref "IC10") (pin "4") (pinfunction "V+_4") (pintype "power_in"))
      (node (ref "IC11") (pin "8") (pinfunction "V+_8") (pintype "power_in"))
      (node (ref "IC12") (pin "4") (pinfunction "V+_4") (pintype "power_in"))
      (node (ref "IC2") (pin "4") (pinfunction "V+_4") (pintype "power_in"))
      (node (ref "IC3") (pin "8") (pinfunction "V+_8") (pintype "power_in"))
      (node (ref "IC4") (pin "11") (pinfunction "V+_11") (pintype "power_in"))
      (node (ref "IC5") (pin "4") (pinfunction "V+_4") (pintype "power_in"))
      (node (ref "IC6") (pin "4") (pinfunction "V+_4") (pintype "power_in"))
      (node (ref "IC7") (pin "8") (pinfunction "V+_8") (pintype "power_in"))
      (node (ref "IC8") (pin "11") (pinfunction "V+_11") (pintype "power_in"))
      (node (ref "IC9") (pin "4") (pinfunction "V+_4") (pintype "power_in"))
      (node (ref "R100") (pin "2") (pinfunction "2_2") (pintype "passive"))
      (node (ref "R120") (pin "1") (pinfunction "1_1") (pintype "passive"))
      (node (ref "R24") (pin "2") (pinfunction "2_2") (pintype "passive"))
      (node (ref "R4") (pin "2") (pinfunction "2_2") (pintype "passive"))
      (node (ref "R42") (pin "2") (pinfunction "2_2") (pintype "passive"))
      (node (ref "R46") (pin "2") (pinfunction "2_2") (pintype "passive"))
      (node (ref "R62") (pin "2") (pinfunction "2_2") (pintype "passive"))
      (node (ref "R8") (pin "2") (pinfunction "2_2") (pintype "passive"))
      (node (ref "R80") (pin "2") (pinfunction "2_2") (pintype "passive"))
      (node (ref "R84") (pin "2") (pinfunction "2_2") (pintype "passive"))
    )
    (net (code "2") (name "-12V") (class "Default")
      (node (ref "C19") (pin "-") (pinfunction "-_-") (pintype "passive"))
      (node (ref "C21") (pin "1") (pinfunction "1_1") (pintype "passive"))
      (node (ref "C23") (pin "1") (pinfunction "1_1") (pintype "passive"))
      (node (ref "C25") (pin "1") (pinfunction "1_1") (pintype "passive"))
      (node (ref "C27") (pin "1") (pinfunction "1_1") (pintype "passive"))
      (node (ref "C29") (pin "1") (pinfunction "1_1") (pintype "passive"))
      (node (ref "D8") (pin "A") (pinfunction "A_A") (pintype "passive"))
      (node (ref "IC1") (pin "11") (pinfunction "V-_11") (pintype "power_in"))
      (node (ref "IC10") (pin "11") (pinfunction "V-_11") (pintype "power_in"))
      (node (ref "IC11") (pin "4") (pinfunction "V-_4") (pintype "power_in"))
      (node (ref "IC12") (pin "11") (pinfunction "V-_11") (pintype "power_in"))
      (node (ref "IC2") (pin "11") (pinfunction "V-_11") (pintype "power_in"))
      (node (ref "IC3") (pin "4") (pinfunction "V-_4") (pintype "power_in"))
      (node (ref "IC4") (pin "6") (pinfunction "V-_6") (pintype "power_in"))
      (node (ref "IC5") (pin "11") (pinfunction "V-_11") (pintype "power_in"))
      (node (ref "IC6") (pin "11") (pinfunction "V-_11") (pintype "power_in"))
      (node (ref "IC7") (pin "4") (pinfunction "V-_4") (pintype "power_in"))
      (node (ref "IC8") (pin "6") (pinfunction "V-_6") (pintype "power_in"))
      (node (ref "IC9") (pin "11") (pinfunction "V-_11") (pintype "power_in"))
      (node (ref "R104") (pin "2") (pinfunction "2_2") (pintype "passive"))
      (node (ref "R28") (pin "2") (pinfunction "2_2") (pintype "passive"))
      (node (ref "R45") (pin "1") (pinfunction "1_1") (pintype "passive"))
      (node (ref "R66") (pin "2") (pinfunction "2_2") (pintype "passive"))
      (node (ref "R7") (pin "1") (pinfunction "1_1") (pintype "passive"))
      (node (ref "R83") (pin "1") (pinfunction "1_1") (pintype "passive"))
    )
    (net (code "3") (name "/ALLCV") (class "Default")
      (node (ref "JP1") (pin "2") (pinfunction "2_2") (pintype "passive"))
      (node (ref "R134") (pin "1") (pinfunction "1_1") (pintype "passive"))
      (node (ref "R135") (pin "1") (pinfunction "1_1") (pintype "passive"))
    )
    (net (code "4") (name "/CASC1") (class "Default")
      (node (ref "JP2") (pin "2") (pinfunction "2_2") (pintype "passive"))
      (node (ref "R115") (pin "1") (pinfunction "1_1") (pintype "passive"))
    )
    (net (code "5") (name "/CASC2") (class "Default")
      (node (ref "JP4") (pin "1") (pinfunction "1_1") (pintype "passive"))
      (node (ref "R40") (pin "1") (pinfunction "1_1") (pintype "passive"))
    )
    (net (code "6") (name "/CASC3") (class "Default")
      (node (ref "JP6") (pin "1") (pinfunction "1_1") (pintype "passive"))
      (node (ref "R78") (pin "1") (pinfunction "1_1") (pintype "passive"))
    )
    (net (code "7") (name "/CLED+") (class "Default")
      (node (ref "IC12") (pin "7") (pinfunction "OUT_7") (pintype "output"))
      (node (ref "JP8") (pin "4") (pinfunction "4_4") (pintype "passive"))
    )
    (net (code "8") (name "/CLED-") (class "Default")
      (node (ref "JP8") (pin "5") (pinfunction "5_5") (pintype "passive"))
      (node (ref "R139") (pin "1") (pinfunction "1_1") (pintype "passive"))
    )
    (net (code "9") (name "/CMB") (class "Default")
      (node (ref "JP8") (pin "6") (pinfunction "6_6") (pintype "passive"))
      (node (ref "R126") (pin "1") (pinfunction "1_1") (pintype "passive"))
    )
    (net (code "10") (name "/CV") (class "Default")
      (node (ref "JP1") (pin "3") (pinfunction "3_3") (pintype "passive"))
      (node (ref "JP2") (pin "1") (pinfunction "1_1") (pintype "passive"))
      (node (ref "R2") (pin "1") (pinfunction "1_1") (pintype "passive"))
    )
    (net (code "11") (name "/FLT") (class "Default")
      (node (ref "D9") (pin "C") (pinfunction "C_C") (pintype "passive"))
      (node (ref "JP8") (pin "1") (pinfunction "1_1") (pintype "passive"))
    )
    (net (code "12") (name "/FLTLED") (class "Default")
      (node (ref "JP8") (pin "2") (pinfunction "2_2") (pintype "passive"))
      (node (ref "R127") (pin "2") (pinfunction "2_2") (pintype "passive"))
    )
    (net (code "13") (name "/LED1") (class "Default")
      (node (ref "JP3") (pin "1") (pinfunction "1_1") (pintype "passive"))
      (node (ref "R38") (pin "2") (pinfunction "2_2") (pintype "passive"))
    )
    (net (code "14") (name "/LED2") (class "Default")
      (node (ref "JP5") (pin "1") (pinfunction "1_1") (pintype "passive"))
      (node (ref "R76") (pin "2") (pinfunction "2_2") (pintype "passive"))
    )
    (net (code "15") (name "/LED3") (class "Default")
      (node (ref "JP7") (pin "1") (pinfunction "1_1") (pintype "passive"))
      (node (ref "R114") (pin "2") (pinfunction "2_2") (pintype "passive"))
    )
    (net (code "16") (name "/RATE1") (class "Default")
      (node (ref "JP2") (pin "3") (pinfunction "3_3") (pintype "passive"))
      (node (ref "R1") (pin "1") (pinfunction "1_1") (pintype "passive"))
    )
    (net (code "17") (name "/RATE2") (class "Default")
      (node (ref "JP4") (pin "2") (pinfunction "2_2") (pintype "passive"))
      (node (ref "R39") (pin "1") (pinfunction "1_1") (pintype "passive"))
    )
    (net (code "18") (name "/RATE3") (class "Default")
      (node (ref "JP6") (pin "2") (pinfunction "2_2") (pintype "passive"))
      (node (ref "R77") (pin "1") (pinfunction "1_1") (pintype "passive"))
    )
    (net (code "19") (name "/RATEH1") (class "Default")
      (node (ref "JP2") (pin "5") (pinfunction "5_5") (pintype "passive"))
      (node (ref "R8") (pin "1") (pinfunction "1_1") (pintype "passive"))
    )
    (net (code "20") (name "/RATEH2") (class "Default")
      (node (ref "JP4") (pin "4") (pinfunction "4_4") (pintype "passive"))
      (node (ref "R46") (pin "1") (pinfunction "1_1") (pintype "passive"))
    )
    (net (code "21") (name "/RATEH3") (class "Default")
      (node (ref "JP6") (pin "4") (pinfunction "4_4") (pintype "passive"))
      (node (ref "R84") (pin "1") (pinfunction "1_1") (pintype "passive"))
    )
    (net (code "22") (name "/RATEL1") (class "Default")
      (node (ref "JP2") (pin "4") (pinfunction "4_4") (pintype "passive"))
      (node (ref "R7") (pin "2") (pinfunction "2_2") (pintype "passive"))
    )
    (net (code "23") (name "/RATEL2") (class "Default")
      (node (ref "JP4") (pin "3") (pinfunction "3_3") (pintype "passive"))
      (node (ref "R45") (pin "2") (pinfunction "2_2") (pintype "passive"))
    )
    (net (code "24") (name "/RATEL3") (class "Default")
      (node (ref "JP6") (pin "3") (pinfunction "3_3") (pintype "passive"))
      (node (ref "R83") (pin "2") (pinfunction "2_2") (pintype "passive"))
    )
    (net (code "25") (name "/RMP1") (class "Default")
      (node (ref "JP3") (pin "5") (pinfunction "5_5") (pintype "passive"))
      (node (ref "R35") (pin "2") (pinfunction "2_2") (pintype "passive"))
    )
    (net (code "26") (name "/RMP2") (class "Default")
      (node (ref "JP5") (pin "5") (pinfunction "5_5") (pintype "passive"))
      (node (ref "R111") (pin "2") (pinfunction "2_2") (pintype "passive"))
    )
    (net (code "27") (name "/RMP3") (class "Default")
      (node (ref "JP7") (pin "5") (pinfunction "5_5") (pintype "passive"))
      (node (ref "R73") (pin "2") (pinfunction "2_2") (pintype "passive"))
    )
    (net (code "28") (name "/RNGCOM1") (class "Default")
      (node (ref "C2") (pin "1") (pinfunction "1_1") (pintype "passive"))
      (node (ref "IC1") (pin "13") (pinfunction "-IN_13") (pintype "input"))
      (node (ref "JP2") (pin "10") (pinfunction "10_10") (pintype "passive"))
      (node (ref "R9") (pin "2") (pinfunction "2_2") (pintype "passive"))
    )
    (net (code "29") (name "/RNGCOM2") (class "Default")
      (node (ref "C5") (pin "1") (pinfunction "1_1") (pintype "passive"))
      (node (ref "IC5") (pin "13") (pinfunction "-IN_13") (pintype "input"))
      (node (ref "JP4") (pin "8") (pinfunction "8_8") (pintype "passive"))
      (node (ref "R47") (pin "2") (pinfunction "2_2") (pintype "passive"))
    )
    (net (code "30") (name "/RNGCOM3") (class "Default")
      (node (ref "C8") (pin "1") (pinfunction "1_1") (pintype "passive"))
      (node (ref "IC9") (pin "13") (pinfunction "-IN_13") (pintype "input"))
      (node (ref "JP6") (pin "8") (pinfunction "8_8") (pintype "passive"))
      (node (ref "R85") (pin "2") (pinfunction "2_2") (pintype "passive"))
    )
    (net (code "31") (name "/RNGL1") (class "Default")
      (node (ref "C11") (pin "1") (pinfunction "1_1") (pintype "passive"))
      (node (ref "JP2") (pin "8") (pinfunction "8_8") (pintype "passive"))
    )
    (net (code "32") (name "/RNGL2") (class "Default")
      (node (ref "C15") (pin "1") (pinfunction "1_1") (pintype "passive"))
      (node (ref "JP4") (pin "6") (pinfunction "6_6") (pintype "passive"))
    )
    (net (code "33") (name "/RNGL3") (class "Default")
      (node (ref "C13") (pin "1") (pinfunction "1_1") (pintype "passive"))
      (node (ref "JP6") (pin "6") (pinfunction "6_6") (pintype "passive"))
    )
    (net (code "34") (name "/RNGM1") (class "Default")
      (node (ref "C10") (pin "1") (pinfunction "1_1") (pintype "passive"))
      (node (ref "JP2") (pin "9") (pinfunction "9_9") (pintype "passive"))
    )
    (net (code "35") (name "/RNGM2") (class "Default")
      (node (ref "C14") (pin "1") (pinfunction "1_1") (pintype "passive"))
      (node (ref "JP4") (pin "7") (pinfunction "7_7") (pintype "passive"))
    )
    (net (code "36") (name "/RNGM3") (class "Default")
      (node (ref "C12") (pin "1") (pinfunction "1_1") (pintype "passive"))
      (node (ref "JP6") (pin "7") (pinfunction "7_7") (pintype "passive"))
    )
    (net (code "37") (name "/SAW1") (class "Default")
      (node (ref "JP3") (pin "6") (pinfunction "6_6") (pintype "passive"))
      (node (ref "R32") (pin "2") (pinfunction "2_2") (pintype "passive"))
    )
    (net (code "38") (name "/SAW2") (class "Default")
      (node (ref "JP5") (pin "6") (pinfunction "6_6") (pintype "passive"))
      (node (ref "R108") (pin "2") (pinfunction "2_2") (pintype "passive"))
    )
    (net (code "39") (name "/SAW3") (class "Default")
      (node (ref "JP7") (pin "6") (pinfunction "6_6") (pintype "passive"))
      (node (ref "R70") (pin "2") (pinfunction "2_2") (pintype "passive"))
    )
    (net (code "40") (name "/SQR1") (class "Default")
      (node (ref "JP3") (pin "8") (pinfunction "8_8") (pintype "passive"))
      (node (ref "R37") (pin "2") (pinfunction "2_2") (pintype "passive"))
    )
    (net (code "41") (name "/SQR2") (class "Default")
      (node (ref "JP5") (pin "8") (pinfunction "8_8") (pintype "passive"))
      (node (ref "R113") (pin "2") (pinfunction "2_2") (pintype "passive"))
    )
    (net (code "42") (name "/SQR3") (class "Default")
      (node (ref "JP7") (pin "8") (pinfunction "8_8") (pintype "passive"))
      (node (ref "R75") (pin "2") (pinfunction "2_2") (pintype "passive"))
    )
    (net (code "43") (name "/TRI1") (class "Default")
      (node (ref "JP3") (pin "4") (pinfunction "4_4") (pintype "passive"))
      (node (ref "R140") (pin "1") (pinfunction "1_1") (pintype "passive"))
      (node (ref "R36") (pin "2") (pinfunction "2_2") (pintype "passive"))
    )
    (net (code "44") (name "/TRI2") (class "Default")
      (node (ref "JP5") (pin "4") (pinfunction "4_4") (pintype "passive"))
      (node (ref "R112") (pin "2") (pinfunction "2_2") (pintype "passive"))
      (node (ref "R117") (pin "1") (pinfunction "1_1") (pintype "passive"))
    )
    (net (code "45") (name "/TRI3") (class "Default")
      (node (ref "JP7") (pin "4") (pinfunction "4_4") (pintype "passive"))
      (node (ref "R122") (pin "1") (pinfunction "1_1") (pintype "passive"))
      (node (ref "R74") (pin "2") (pinfunction "2_2") (pintype "passive"))
    )
    (net (code "46") (name "GND") (class "Default")
      (node (ref "C18") (pin "-") (pinfunction "-_-") (pintype "passive"))
      (node (ref "C19") (pin "+") (pinfunction "+_+") (pintype "passive"))
      (node (ref "C20") (pin "1") (pinfunction "1_1") (pintype "passive"))
      (node (ref "C21") (pin "2") (pinfunction "2_2") (pintype "passive"))
      (node (ref "C22") (pin "1") (pinfunction "1_1") (pintype "passive"))
      (node (ref "C23") (pin "2") (pinfunction "2_2") (pintype "passive"))
      (node (ref "C24") (pin "1") (pinfunction "1_1") (pintype "passive"))
      (node (ref "C25") (pin "2") (pinfunction "2_2") (pintype "passive"))
      (node (ref "C26") (pin "1") (pinfunction "1_1") (pintype "passive"))
      (node (ref "C27") (pin "2") (pinfunction "2_2") (pintype "passive"))
      (node (ref "C28") (pin "1") (pinfunction "1_1") (pintype "passive"))
      (node (ref "C29") (pin "2") (pinfunction "2_2") (pintype "passive"))
      (node (ref "IC1") (pin "10") (pinfunction "+IN_10") (pintype "input"))
      (node (ref "IC1") (pin "12") (pinfunction "+IN_12") (pintype "input"))
      (node (ref "IC1") (pin "2") (pinfunction "-IN_2") (pintype "input"))
      (node (ref "IC1") (pin "5") (pinfunction "+IN_5") (pintype "input"))
      (node (ref "IC10") (pin "5") (pinfunction "+IN_5") (pintype "input"))
      (node (ref "IC11") (pin "3") (pinfunction "+IN_3") (pintype "input"))
      (node (ref "IC11") (pin "5") (pinfunction "+IN_5") (pintype "input"))
      (node (ref "IC12") (pin "12") (pinfunction "+IN_12") (pintype "input"))
      (node (ref "IC12") (pin "2") (pinfunction "-IN_2") (pintype "input"))
      (node (ref "IC12") (pin "5") (pinfunction "+IN_5") (pintype "input"))
      (node (ref "IC12") (pin "9") (pinfunction "-IN_9") (pintype "input"))
      (node (ref "IC2") (pin "5") (pinfunction "+IN_5") (pintype "input"))
      (node (ref "IC3") (pin "3") (pinfunction "+IN_3") (pintype "input"))
      (node (ref "IC3") (pin "5") (pinfunction "+IN_5") (pintype "input"))
      (node (ref "IC4") (pin "13") (pinfunction "IN_N_13") (pintype "input"))
      (node (ref "IC4") (pin "4") (pinfunction "IN_N_4") (pintype "input"))
      (node (ref "IC5") (pin "10") (pinfunction "+IN_10") (pintype "input"))
      (node (ref "IC5") (pin "12") (pinfunction "+IN_12") (pintype "input"))
      (node (ref "IC5") (pin "2") (pinfunction "-IN_2") (pintype "input"))
      (node (ref "IC5") (pin "5") (pinfunction "+IN_5") (pintype "input"))
      (node (ref "IC6") (pin "5") (pinfunction "+IN_5") (pintype "input"))
      (node (ref "IC7") (pin "3") (pinfunction "+IN_3") (pintype "input"))
      (node (ref "IC7") (pin "5") (pinfunction "+IN_5") (pintype "input"))
      (node (ref "IC8") (pin "13") (pinfunction "IN_N_13") (pintype "input"))
      (node (ref "IC9") (pin "10") (pinfunction "+IN_10") (pintype "input"))
      (node (ref "IC9") (pin "12") (pinfunction "+IN_12") (pintype "input"))
      (node (ref "IC9") (pin "2") (pinfunction "-IN_2") (pintype "input"))
      (node (ref "IC9") (pin "5") (pinfunction "+IN_5") (pintype "input"))
      (node (ref "JP2") (pin "6") (pinfunction "6_6") (pintype "passive"))
      (node (ref "JP2") (pin "7") (pinfunction "7_7") (pintype "passive"))
      (node (ref "JP3") (pin "2") (pinfunction "2_2") (pintype "passive"))
      (node (ref "JP3") (pin "3") (pinfunction "3_3") (pintype "passive"))
      (node (ref "JP3") (pin "7") (pinfunction "7_7") (pintype "passive"))
      (node (ref "JP4") (pin "5") (pinfunction "5_5") (pintype "passive"))
      (node (ref "JP5") (pin "2") (pinfunction "2_2") (pintype "passive"))
      (node (ref "JP5") (pin "3") (pinfunction "3_3") (pintype "passive"))
      (node (ref "JP5") (pin "7") (pinfunction "7_7") (pintype "passive"))
      (node (ref "JP6") (pin "5") (pinfunction "5_5") (pintype "passive"))
      (node (ref "JP7") (pin "2") (pinfunction "2_2") (pintype "passive"))
      (node (ref "JP7") (pin "3") (pinfunction "3_3") (pintype "passive"))
      (node (ref "JP7") (pin "7") (pinfunction "7_7") (pintype "passive"))
      (node (ref "JP8") (pin "3") (pinfunction "3_3") (pintype "passive"))
      (node (ref "R105") (pin "2") (pinfunction "2_2") (pintype "passive"))
      (node (ref "R107") (pin "2") (pinfunction "2_2") (pintype "passive"))
      (node (ref "R119") (pin "1") (pinfunction "1_1") (pintype "passive"))
      (node (ref "R123") (pin "1") (pinfunction "1_1") (pintype "passive"))
      (node (ref "R124") (pin "1") (pinfunction "1_1") (pintype "passive"))
      (node (ref "R129") (pin "1") (pinfunction "1_1") (pintype "passive"))
      (node (ref "R131") (pin "1") (pinfunction "1_1") (pintype "passive"))
      (node (ref "R133") (pin "1") (pinfunction "1_1") (pintype "passive"))
      (node (ref "R14") (pin "1") (pinfunction "1_1") (pintype "passive"))
      (node (ref "R29") (pin "2") (pinfunction "2_2") (pintype "passive"))
      (node (ref "R31") (pin "2") (pinfunction "2_2") (pintype "passive"))
      (node (ref "R52") (pin "1") (pinfunction "1_1") (pintype "passive"))
      (node (ref "R67") (pin "2") (pinfunction "2_2") (pintype "passive"))
      (node (ref "R69") (pin "2") (pinfunction "2_2") (pintype "passive"))
      (node (ref "R90") (pin "1") (pinfunction "1_1") (pintype "passive"))
      (node (ref "SV1") (pin "3") (pinfunction "3_3") (pintype "passive"))
      (node (ref "SV1") (pin "4") (pinfunction "4_4") (pintype "passive"))
      (node (ref "SV1") (pin "5") (pinfunction "5_5") (pintype "passive"))
      (node (ref "SV1") (pin "6") (pinfunction "6_6") (pintype "passive"))
      (node (ref "SV1") (pin "7") (pinfunction "7_7") (pintype "passive"))
      (node (ref "SV1") (pin "8") (pinfunction "8_8") (pintype "passive"))
      (node (ref "T1") (pin "C") (pinfunction "C_C") (pintype "passive"))
      (node (ref "T3") (pin "B") (pinfunction "B_B") (pintype "passive"))
      (node (ref "T4") (pin "C") (pinfunction "C_C") (pintype "passive"))
      (node (ref "T6") (pin "B") (pinfunction "B_B") (pintype "passive"))
      (node (ref "T7") (pin "C") (pinfunction "C_C") (pintype "passive"))
      (node (ref "T9") (pin "B") (pinfunction "B_B") (pintype "passive"))
    )
    (net (code "47") (name "Net-(D1-PadA)") (class "Default")
      (node (ref "D1") (pin "A") (pinfunction "A_A") (pintype "passive"))
      (node (ref "R12") (pin "2") (pinfunction "2_2") (pintype "passive"))
    )
    (net (code "48") (name "Net-(D2-PadC)") (class "Default")
      (node (ref "D2") (pin "C") (pinfunction "C_C") (pintype "passive"))
      (node (ref "R13") (pin "2") (pinfunction "2_2") (pintype "passive"))
    )
    (net (code "49") (name "Net-(D3-PadA)") (class "Default")
      (node (ref "D3") (pin "A") (pinfunction "A_A") (pintype "passive"))
      (node (ref "R50") (pin "2") (pinfunction "2_2") (pintype "passive"))
    )
    (net (code "50") (name "Net-(D4-PadC)") (class "Default")
      (node (ref "D4") (pin "C") (pinfunction "C_C") (pintype "passive"))
      (node (ref "R51") (pin "2") (pinfunction "2_2") (pintype "passive"))
    )
    (net (code "51") (name "Net-(D5-PadA)") (class "Default")
      (node (ref "D5") (pin "A") (pinfunction "A_A") (pintype "passive"))
      (node (ref "R88") (pin "2") (pinfunction "2_2") (pintype "passive"))
    )
    (net (code "52") (name "Net-(D6-PadC)") (class "Default")
      (node (ref "D6") (pin "C") (pinfunction "C_C") (pintype "passive"))
      (node (ref "R89") (pin "2") (pinfunction "2_2") (pintype "passive"))
    )
    (net (code "53") (name "Net-(D7-PadA)") (class "Default")
      (node (ref "D7") (pin "A") (pinfunction "A_A") (pintype "passive"))
      (node (ref "SV1") (pin "10") (pinfunction "10_10") (pintype "passive"))
      (node (ref "SV1") (pin "9") (pinfunction "9_9") (pintype "passive"))
    )
    (net (code "54") (name "Net-(D8-PadC)") (class "Default")
      (node (ref "D8") (pin "C") (pinfunction "C_C") (pintype "passive"))
      (node (ref "SV1") (pin "1") (pinfunction "1_1") (pintype "passive"))
      (node (ref "SV1") (pin "2") (pinfunction "2_2") (pintype "passive"))
    )
    (net (code "55") (name "Net-(IC1A-+IN)") (class "Default")
      (node (ref "C3") (pin "1") (pinfunction "1_1") (pintype "passive"))
      (node (ref "IC1") (pin "3") (pinfunction "+IN_3") (pintype "input"))
      (node (ref "R10") (pin "2") (pinfunction "2_2") (pintype "passive"))
      (node (ref "R11") (pin "1") (pinfunction "1_1") (pintype "passive"))
    )
    (net (code "56") (name "Net-(IC1A-OUT)") (class "Default")
      (node (ref "C3") (pin "2") (pinfunction "2_2") (pintype "passive"))
      (node (ref "D1") (pin "C") (pinfunction "C_C") (pintype "passive"))
      (node (ref "D2") (pin "A") (pinfunction "A_A") (pintype "passive"))
      (node (ref "IC1") (pin "1") (pinfunction "OUT_1") (pintype "output"))
      (node (ref "R11") (pin "2") (pinfunction "2_2") (pintype "passive"))
      (node (ref "R128") (pin "2") (pinfunction "2_2") (pintype "passive"))
      (node (ref "R16") (pin "1") (pinfunction "1_1") (pintype "passive"))
      (node (ref "R21") (pin "1") (pinfunction "1_1") (pintype "passive"))
    )
    (net (code "57") (name "Net-(IC1B--IN)") (class "Default")
      (node (ref "IC1") (pin "6") (pinfunction "-IN_6") (pintype "input"))
      (node (ref "R16") (pin "2") (pinfunction "2_2") (pintype "passive"))
      (node (ref "R17") (pin "1") (pinfunction "1_1") (pintype "passive"))
    )
    (net (code "58") (name "Net-(IC1B-OUT)") (class "Default")
      (node (ref "IC1") (pin "7") (pinfunction "OUT_7") (pintype "output"))
      (node (ref "R17") (pin "2") (pinfunction "2_2") (pintype "passive"))
      (node (ref "R20") (pin "1") (pinfunction "1_1") (pintype "passive"))
    )
    (net (code "59") (name "Net-(IC1C--IN)") (class "Default")
      (node (ref "IC1") (pin "9") (pinfunction "-IN_9") (pintype "input"))
      (node (ref "R18") (pin "2") (pinfunction "2_2") (pintype "passive"))
      (node (ref "R19") (pin "1") (pinfunction "1_1") (pintype "passive"))
    )
    (net (code "60") (name "Net-(IC1C-OUT)") (class "Default")
      (node (ref "IC1") (pin "8") (pinfunction "OUT_8") (pintype "output"))
      (node (ref "Q4") (pin "2") (pinfunction "S_2") (pintype "passive"))
      (node (ref "R19") (pin "2") (pinfunction "2_2") (pintype "passive"))
    )
    (net (code "61") (name "Net-(IC1D-OUT)") (class "Default")
      (node (ref "C10") (pin "2") (pinfunction "2_2") (pintype "passive"))
      (node (ref "C11") (pin "2") (pinfunction "2_2") (pintype "passive"))
      (node (ref "C2") (pin "2") (pinfunction "2_2") (pintype "passive"))
      (node (ref "IC1") (pin "14") (pinfunction "OUT_14") (pintype "output"))
      (node (ref "IC2") (pin "12") (pinfunction "+IN_12") (pintype "input"))
      (node (ref "Q5") (pin "2") (pinfunction "S_2") (pintype "passive"))
      (node (ref "R10") (pin "1") (pinfunction "1_1") (pintype "passive"))
      (node (ref "R18") (pin "1") (pinfunction "1_1") (pintype "passive"))
    )
    (net (code "62") (name "Net-(IC2A-+IN)") (class "Default")
      (node (ref "IC2") (pin "3") (pinfunction "+IN_3") (pintype "input"))
      (node (ref "IC4") (pin "10") (pinfunction "B_10") (pintype "passive"))
      (node (ref "R128") (pin "1") (pinfunction "1_1") (pintype "passive"))
      (node (ref "R129") (pin "2") (pinfunction "2_2") (pintype "passive"))
    )
    (net (code "63") (name "Net-(IC2A--IN)") (class "Default")
      (node (ref "IC2") (pin "1") (pinfunction "OUT_1") (pintype "output"))
      (node (ref "IC2") (pin "2") (pinfunction "-IN_2") (pintype "input"))
      (node (ref "R37") (pin "1") (pinfunction "1_1") (pintype "passive"))
    )
    (net (code "64") (name "Net-(IC2B--IN)") (class "Default")
      (node (ref "IC2") (pin "6") (pinfunction "-IN_6") (pintype "input"))
      (node (ref "R33") (pin "2") (pinfunction "2_2") (pintype "passive"))
      (node (ref "R34") (pin "1") (pinfunction "1_1") (pintype "passive"))
    )
    (net (code "65") (name "Net-(IC2B-OUT)") (class "Default")
      (node (ref "IC2") (pin "7") (pinfunction "OUT_7") (pintype "output"))
      (node (ref "R34") (pin "2") (pinfunction "2_2") (pintype "passive"))
      (node (ref "R35") (pin "1") (pinfunction "1_1") (pintype "passive"))
    )
    (net (code "66") (name "Net-(IC2C-+IN)") (class "Default")
      (node (ref "IC2") (pin "10") (pinfunction "+IN_10") (pintype "input"))
      (node (ref "R22") (pin "1") (pinfunction "E_1") (pintype "passive"))
      (node (ref "R25") (pin "1") (pinfunction "1_1") (pintype "passive"))
      (node (ref "R29") (pin "1") (pinfunction "1_1") (pintype "passive"))
    )
    (net (code "67") (name "Net-(IC2C--IN)") (class "Default")
      (node (ref "IC2") (pin "9") (pinfunction "-IN_9") (pintype "input"))
      (node (ref "R30") (pin "2") (pinfunction "2_2") (pintype "passive"))
      (node (ref "R31") (pin "1") (pinfunction "1_1") (pintype "passive"))
    )
    (net (code "68") (name "Net-(IC2C-OUT)") (class "Default")
      (node (ref "IC2") (pin "8") (pinfunction "OUT_8") (pintype "output"))
      (node (ref "R30") (pin "1") (pinfunction "1_1") (pintype "passive"))
      (node (ref "R32") (pin "1") (pinfunction "1_1") (pintype "passive"))
      (node (ref "R33") (pin "1") (pinfunction "1_1") (pintype "passive"))
    )
    (net (code "69") (name "Net-(IC2D--IN)") (class "Default")
      (node (ref "IC2") (pin "13") (pinfunction "-IN_13") (pintype "input"))
      (node (ref "IC2") (pin "14") (pinfunction "OUT_14") (pintype "output"))
      (node (ref "R36") (pin "1") (pinfunction "1_1") (pintype "passive"))
    )
    (net (code "70") (name "Net-(IC3A--IN)") (class "Default")
      (node (ref "C1") (pin "1") (pinfunction "1_1") (pintype "passive"))
      (node (ref "IC3") (pin "2") (pinfunction "-IN_2") (pintype "input"))
      (node (ref "R4") (pin "1") (pinfunction "1_1") (pintype "passive"))
      (node (ref "T2") (pin "C") (pinfunction "C_C") (pintype "passive"))
    )
    (net (code "71") (name "Net-(IC3A-OUT)") (class "Default")
      (node (ref "C1") (pin "2") (pinfunction "2_2") (pintype "passive"))
      (node (ref "IC3") (pin "1") (pinfunction "OUT_1") (pintype "output"))
      (node (ref "R5") (pin "1") (pinfunction "1_1") (pintype "passive"))
    )
    (net (code "72") (name "Net-(IC3B--IN)") (class "Default")
      (node (ref "IC3") (pin "6") (pinfunction "-IN_6") (pintype "input"))
      (node (ref "R1") (pin "2") (pinfunction "2_2") (pintype "passive"))
      (node (ref "R115") (pin "2") (pinfunction "2_2") (pintype "passive"))
      (node (ref "R2") (pin "2") (pinfunction "2_2") (pintype "passive"))
      (node (ref "R3") (pin "1") (pinfunction "1_1") (pintype "passive"))
    )
    (net (code "73") (name "Net-(IC3B-OUT)") (class "Default")
      (node (ref "IC3") (pin "7") (pinfunction "OUT_7") (pintype "output"))
      (node (ref "R3") (pin "2") (pinfunction "2_2") (pintype "passive"))
      (node (ref "T2") (pin "B") (pinfunction "B_B") (pintype "passive"))
    )
    (net (code "74") (name "Net-(IC4A-B)") (class "Default")
      (node (ref "IC4") (pin "7") (pinfunction "B_7") (pintype "passive"))
      (node (ref "IC6") (pin "3") (pinfunction "+IN_3") (pintype "input"))
      (node (ref "R130") (pin "1") (pinfunction "1_1") (pintype "passive"))
      (node (ref "R131") (pin "2") (pinfunction "2_2") (pintype "passive"))
    )
    (net (code "75") (name "Net-(IC4A-E)") (class "Default")
      (node (ref "IC4") (pin "8") (pinfunction "E_8") (pintype "passive"))
      (node (ref "R76") (pin "1") (pinfunction "1_1") (pintype "passive"))
    )
    (net (code "76") (name "Net-(IC4B-E)") (class "Default")
      (node (ref "IC4") (pin "9") (pinfunction "E_9") (pintype "passive"))
      (node (ref "R38") (pin "1") (pinfunction "1_1") (pintype "passive"))
    )
    (net (code "77") (name "Net-(IC4C-IN_P)") (class "Default")
      (node (ref "IC4") (pin "3") (pinfunction "IN_P_3") (pintype "input"))
      (node (ref "R52") (pin "2") (pinfunction "2_2") (pintype "passive"))
      (node (ref "R53") (pin "2") (pinfunction "S_2") (pintype "passive"))
    )
    (net (code "78") (name "Net-(IC4C-I_BIAS)") (class "Default")
      (node (ref "IC4") (pin "1") (pinfunction "I_BIAS_1") (pintype "input"))
      (node (ref "R44") (pin "1") (pinfunction "1_1") (pintype "passive"))
    )
    (net (code "79") (name "Net-(IC4C-OUT)") (class "Default")
      (node (ref "IC4") (pin "5") (pinfunction "OUT_5") (pintype "output"))
      (node (ref "R47") (pin "1") (pinfunction "1_1") (pintype "passive"))
    )
    (net (code "80") (name "Net-(IC4D-IN_P)") (class "Default")
      (node (ref "IC4") (pin "14") (pinfunction "IN_P_14") (pintype "input"))
      (node (ref "R14") (pin "2") (pinfunction "2_2") (pintype "passive"))
      (node (ref "R15") (pin "2") (pinfunction "S_2") (pintype "passive"))
    )
    (net (code "81") (name "Net-(IC4D-I_BIAS)") (class "Default")
      (node (ref "IC4") (pin "16") (pinfunction "I_BIAS_16") (pintype "input"))
      (node (ref "R6") (pin "1") (pinfunction "1_1") (pintype "passive"))
    )
    (net (code "82") (name "Net-(IC4D-OUT)") (class "Default")
      (node (ref "IC4") (pin "12") (pinfunction "OUT_12") (pintype "output"))
      (node (ref "R9") (pin "1") (pinfunction "1_1") (pintype "passive"))
    )
    (net (code "83") (name "Net-(IC5A-+IN)") (class "Default")
      (node (ref "C6") (pin "1") (pinfunction "1_1") (pintype "passive"))
      (node (ref "IC5") (pin "3") (pinfunction "+IN_3") (pintype "input"))
      (node (ref "R48") (pin "2") (pinfunction "2_2") (pintype "passive"))
      (node (ref "R49") (pin "1") (pinfunction "1_1") (pintype "passive"))
    )
    (net (code "84") (name "Net-(IC5A-OUT)") (class "Default")
      (node (ref "C6") (pin "2") (pinfunction "2_2") (pintype "passive"))
      (node (ref "D3") (pin "C") (pinfunction "C_C") (pintype "passive"))
      (node (ref "D4") (pin "A") (pinfunction "A_A") (pintype "passive"))
      (node (ref "IC5") (pin "1") (pinfunction "OUT_1") (pintype "output"))
      (node (ref "R130") (pin "2") (pinfunction "2_2") (pintype "passive"))
      (node (ref "R49") (pin "2") (pinfunction "2_2") (pintype "passive"))
      (node (ref "R54") (pin "1") (pinfunction "1_1") (pintype "passive"))
      (node (ref "R59") (pin "1") (pinfunction "1_1") (pintype "passive"))
    )
    (net (code "85") (name "Net-(IC5B--IN)") (class "Default")
      (node (ref "IC5") (pin "6") (pinfunction "-IN_6") (pintype "input"))
      (node (ref "R54") (pin "2") (pinfunction "2_2") (pintype "passive"))
      (node (ref "R55") (pin "1") (pinfunction "1_1") (pintype "passive"))
    )
    (net (code "86") (name "Net-(IC5B-OUT)") (class "Default")
      (node (ref "IC5") (pin "7") (pinfunction "OUT_7") (pintype "output"))
      (node (ref "R55") (pin "2") (pinfunction "2_2") (pintype "passive"))
      (node (ref "R58") (pin "1") (pinfunction "1_1") (pintype "passive"))
    )
    (net (code "87") (name "Net-(IC5C--IN)") (class "Default")
      (node (ref "IC5") (pin "9") (pinfunction "-IN_9") (pintype "input"))
      (node (ref "R56") (pin "2") (pinfunction "2_2") (pintype "passive"))
      (node (ref "R57") (pin "1") (pinfunction "1_1") (pintype "passive"))
    )
    (net (code "88") (name "Net-(IC5C-OUT)") (class "Default")
      (node (ref "IC5") (pin "8") (pinfunction "OUT_8") (pintype "output"))
      (node (ref "Q1") (pin "2") (pinfunction "S_2") (pintype "passive"))
      (node (ref "R57") (pin "2") (pinfunction "2_2") (pintype "passive"))
    )
    (net (code "89") (name "Net-(IC5D-OUT)") (class "Default")
      (node (ref "C14") (pin "2") (pinfunction "2_2") (pintype "passive"))
      (node (ref "C15") (pin "2") (pinfunction "2_2") (pintype "passive"))
      (node (ref "C5") (pin "2") (pinfunction "2_2") (pintype "passive"))
      (node (ref "IC5") (pin "14") (pinfunction "OUT_14") (pintype "output"))
      (node (ref "IC6") (pin "12") (pinfunction "+IN_12") (pintype "input"))
      (node (ref "Q2") (pin "2") (pinfunction "S_2") (pintype "passive"))
      (node (ref "R48") (pin "1") (pinfunction "1_1") (pintype "passive"))
      (node (ref "R56") (pin "1") (pinfunction "1_1") (pintype "passive"))
    )
    (net (code "90") (name "Net-(IC6A--IN)") (class "Default")
      (node (ref "IC6") (pin "1") (pinfunction "OUT_1") (pintype "output"))
      (node (ref "IC6") (pin "2") (pinfunction "-IN_2") (pintype "input"))
      (node (ref "R113") (pin "1") (pinfunction "1_1") (pintype "passive"))
    )
    (net (code "91") (name "Net-(IC6B--IN)") (class "Default")
      (node (ref "IC6") (pin "6") (pinfunction "-IN_6") (pintype "input"))
      (node (ref "R71") (pin "2") (pinfunction "2_2") (pintype "passive"))
      (node (ref "R72") (pin "1") (pinfunction "1_1") (pintype "passive"))
    )
    (net (code "92") (name "Net-(IC6B-OUT)") (class "Default")
      (node (ref "IC6") (pin "7") (pinfunction "OUT_7") (pintype "output"))
      (node (ref "R111") (pin "1") (pinfunction "1_1") (pintype "passive"))
      (node (ref "R72") (pin "2") (pinfunction "2_2") (pintype "passive"))
    )
    (net (code "93") (name "Net-(IC6C-+IN)") (class "Default")
      (node (ref "IC6") (pin "10") (pinfunction "+IN_10") (pintype "input"))
      (node (ref "R60") (pin "1") (pinfunction "E_1") (pintype "passive"))
      (node (ref "R63") (pin "1") (pinfunction "1_1") (pintype "passive"))
      (node (ref "R67") (pin "1") (pinfunction "1_1") (pintype "passive"))
    )
    (net (code "94") (name "Net-(IC6C--IN)") (class "Default")
      (node (ref "IC6") (pin "9") (pinfunction "-IN_9") (pintype "input"))
      (node (ref "R68") (pin "2") (pinfunction "2_2") (pintype "passive"))
      (node (ref "R69") (pin "1") (pinfunction "1_1") (pintype "passive"))
    )
    (net (code "95") (name "Net-(IC6C-OUT)") (class "Default")
      (node (ref "IC6") (pin "8") (pinfunction "OUT_8") (pintype "output"))
      (node (ref "R108") (pin "1") (pinfunction "1_1") (pintype "passive"))
      (node (ref "R68") (pin "1") (pinfunction "1_1") (pintype "passive"))
      (node (ref "R71") (pin "1") (pinfunction "1_1") (pintype "passive"))
    )
    (net (code "96") (name "Net-(IC6D--IN)") (class "Default")
      (node (ref "IC6") (pin "13") (pinfunction "-IN_13") (pintype "input"))
      (node (ref "IC6") (pin "14") (pinfunction "OUT_14") (pintype "output"))
      (node (ref "R112") (pin "1") (pinfunction "1_1") (pintype "passive"))
    )
    (net (code "97") (name "Net-(IC7A--IN)") (class "Default")
      (node (ref "IC7") (pin "2") (pinfunction "-IN_2") (pintype "input"))
      (node (ref "R134") (pin "2") (pinfunction "2_2") (pintype "passive"))
      (node (ref "R39") (pin "2") (pinfunction "2_2") (pintype "passive"))
      (node (ref "R40") (pin "2") (pinfunction "2_2") (pintype "passive"))
      (node (ref "R41") (pin "1") (pinfunction "1_1") (pintype "passive"))
    )
    (net (code "98") (name "Net-(IC7A-OUT)") (class "Default")
      (node (ref "IC7") (pin "1") (pinfunction "OUT_1") (pintype "output"))
      (node (ref "R41") (pin "2") (pinfunction "2_2") (pintype "passive"))
      (node (ref "T5") (pin "B") (pinfunction "B_B") (pintype "passive"))
    )
    (net (code "99") (name "Net-(IC7B--IN)") (class "Default")
      (node (ref "C4") (pin "1") (pinfunction "1_1") (pintype "passive"))
      (node (ref "IC7") (pin "6") (pinfunction "-IN_6") (pintype "input"))
      (node (ref "R42") (pin "1") (pinfunction "1_1") (pintype "passive"))
      (node (ref "T5") (pin "C") (pinfunction "C_C") (pintype "passive"))
    )
    (net (code "100") (name "Net-(IC7B-OUT)") (class "Default")
      (node (ref "C4") (pin "2") (pinfunction "2_2") (pintype "passive"))
      (node (ref "IC7") (pin "7") (pinfunction "OUT_7") (pintype "output"))
      (node (ref "R43") (pin "1") (pinfunction "1_1") (pintype "passive"))
    )
    (net (code "101") (name "Net-(IC8A-E)") (class "Default")
      (node (ref "IC8") (pin "8") (pinfunction "E_8") (pintype "passive"))
      (node (ref "R127") (pin "1") (pinfunction "1_1") (pintype "passive"))
    )
    (net (code "102") (name "Net-(IC8B-E)") (class "Default")
      (node (ref "IC8") (pin "9") (pinfunction "E_9") (pintype "passive"))
      (node (ref "R114") (pin "1") (pinfunction "1_1") (pintype "passive"))
    )
    (net (code "103") (name "Net-(IC8C-IN_N)") (class "Default")
      (node (ref "IC8") (pin "4") (pinfunction "IN_N_4") (pintype "input"))
      (node (ref "R122") (pin "2") (pinfunction "2_2") (pintype "passive"))
      (node (ref "R123") (pin "2") (pinfunction "2_2") (pintype "passive"))
    )
    (net (code "104") (name "Net-(IC8C-IN_P)") (class "Default")
      (node (ref "IC8") (pin "3") (pinfunction "IN_P_3") (pintype "input"))
      (node (ref "R124") (pin "2") (pinfunction "2_2") (pintype "passive"))
    )
    (net (code "105") (name "Net-(IC8C-I_BIAS)") (class "Default")
      (node (ref "IC8") (pin "1") (pinfunction "I_BIAS_1") (pintype "input"))
      (node (ref "T10") (pin "C") (pinfunction "C_C") (pintype "passive"))
    )
    (net (code "106") (name "Net-(IC8D-IN_P)") (class "Default")
      (node (ref "IC8") (pin "14") (pinfunction "IN_P_14") (pintype "input"))
      (node (ref "R90") (pin "2") (pinfunction "2_2") (pintype "passive"))
      (node (ref "R91") (pin "2") (pinfunction "S_2") (pintype "passive"))
    )
    (net (code "107") (name "Net-(IC8D-I_BIAS)") (class "Default")
      (node (ref "IC8") (pin "16") (pinfunction "I_BIAS_16") (pintype "input"))
      (node (ref "R82") (pin "1") (pinfunction "1_1") (pintype "passive"))
    )
    (net (code "108") (name "Net-(IC8D-OUT)") (class "Default")
      (node (ref "IC8") (pin "12") (pinfunction "OUT_12") (pintype "output"))
      (node (ref "R85") (pin "1") (pinfunction "1_1") (pintype "passive"))
    )
    (net (code "109") (name "Net-(IC9A-+IN)") (class "Default")
      (node (ref "C9") (pin "1") (pinfunction "1_1") (pintype "passive"))
      (node (ref "IC9") (pin "3") (pinfunction "+IN_3") (pintype "input"))
      (node (ref "R86") (pin "2") (pinfunction "2_2") (pintype "passive"))
      (node (ref "R87") (pin "1") (pinfunction "1_1") (pintype "passive"))
    )
    (net (code "110") (name "Net-(IC9A-OUT)") (class "Default")
      (node (ref "C9") (pin "2") (pinfunction "2_2") (pintype "passive"))
      (node (ref "D5") (pin "C") (pinfunction "C_C") (pintype "passive"))
      (node (ref "D6") (pin "A") (pinfunction "A_A") (pintype "passive"))
      (node (ref "IC9") (pin "1") (pinfunction "OUT_1") (pintype "output"))
      (node (ref "R132") (pin "2") (pinfunction "2_2") (pintype "passive"))
      (node (ref "R87") (pin "2") (pinfunction "2_2") (pintype "passive"))
      (node (ref "R92") (pin "1") (pinfunction "1_1") (pintype "passive"))
      (node (ref "R97") (pin "1") (pinfunction "1_1") (pintype "passive"))
    )
    (net (code "111") (name "Net-(IC9B--IN)") (class "Default")
      (node (ref "IC9") (pin "6") (pinfunction "-IN_6") (pintype "input"))
      (node (ref "R92") (pin "2") (pinfunction "2_2") (pintype "passive"))
      (node (ref "R93") (pin "1") (pinfunction "1_1") (pintype "passive"))
    )
    (net (code "112") (name "Net-(IC9B-OUT)") (class "Default")
      (node (ref "IC9") (pin "7") (pinfunction "OUT_7") (pintype "output"))
      (node (ref "R93") (pin "2") (pinfunction "2_2") (pintype "passive"))
      (node (ref "R96") (pin "1") (pinfunction "1_1") (pintype "passive"))
    )
    (net (code "113") (name "Net-(IC9C--IN)") (class "Default")
      (node (ref "IC9") (pin "9") (pinfunction "-IN_9") (pintype "input"))
      (node (ref "R94") (pin "2") (pinfunction "2_2") (pintype "passive"))
      (node (ref "R95") (pin "1") (pinfunction "1_1") (pintype "passive"))
    )
    (net (code "114") (name "Net-(IC9C-OUT)") (class "Default")
      (node (ref "IC9") (pin "8") (pinfunction "OUT_8") (pintype "output"))
      (node (ref "Q3") (pin "2") (pinfunction "S_2") (pintype "passive"))
      (node (ref "R95") (pin "2") (pinfunction "2_2") (pintype "passive"))
    )
    (net (code "115") (name "Net-(IC10A-+IN)") (class "Default")
      (node (ref "IC10") (pin "3") (pinfunction "+IN_3") (pintype "input"))
      (node (ref "IC8") (pin "10") (pinfunction "B_10") (pintype "passive"))
      (node (ref "R132") (pin "1") (pinfunction "1_1") (pintype "passive"))
      (node (ref "R133") (pin "2") (pinfunction "2_2") (pintype "passive"))
    )
    (net (code "116") (name "Net-(IC10A--IN)") (class "Default")
      (node (ref "IC10") (pin "1") (pinfunction "OUT_1") (pintype "output"))
      (node (ref "IC10") (pin "2") (pinfunction "-IN_2") (pintype "input"))
      (node (ref "R75") (pin "1") (pinfunction "1_1") (pintype "passive"))
    )
    (net (code "117") (name "Net-(IC10B--IN)") (class "Default")
      (node (ref "IC10") (pin "6") (pinfunction "-IN_6") (pintype "input"))
      (node (ref "R109") (pin "2") (pinfunction "2_2") (pintype "passive"))
      (node (ref "R110") (pin "1") (pinfunction "1_1") (pintype "passive"))
    )
    (net (code "118") (name "Net-(IC10B-OUT)") (class "Default")
      (node (ref "IC10") (pin "7") (pinfunction "OUT_7") (pintype "output"))
      (node (ref "R110") (pin "2") (pinfunction "2_2") (pintype "passive"))
      (node (ref "R73") (pin "1") (pinfunction "1_1") (pintype "passive"))
    )
    (net (code "119") (name "Net-(IC10C-+IN)") (class "Default")
      (node (ref "IC10") (pin "10") (pinfunction "+IN_10") (pintype "input"))
      (node (ref "R101") (pin "1") (pinfunction "1_1") (pintype "passive"))
      (node (ref "R105") (pin "1") (pinfunction "1_1") (pintype "passive"))
      (node (ref "R98") (pin "1") (pinfunction "E_1") (pintype "passive"))
    )
    (net (code "120") (name "Net-(IC10C--IN)") (class "Default")
      (node (ref "IC10") (pin "9") (pinfunction "-IN_9") (pintype "input"))
      (node (ref "R106") (pin "2") (pinfunction "2_2") (pintype "passive"))
      (node (ref "R107") (pin "1") (pinfunction "1_1") (pintype "passive"))
    )
    (net (code "121") (name "Net-(IC10C-OUT)") (class "Default")
      (node (ref "IC10") (pin "8") (pinfunction "OUT_8") (pintype "output"))
      (node (ref "R106") (pin "1") (pinfunction "1_1") (pintype "passive"))
      (node (ref "R109") (pin "1") (pinfunction "1_1") (pintype "passive"))
      (node (ref "R70") (pin "1") (pinfunction "1_1") (pintype "passive"))
    )
    (net (code "122") (name "Net-(IC10D-+IN)") (class "Default")
      (node (ref "C12") (pin "2") (pinfunction "2_2") (pintype "passive"))
      (node (ref "C13") (pin "2") (pinfunction "2_2") (pintype "passive"))
      (node (ref "C8") (pin "2") (pinfunction "2_2") (pintype "passive"))
      (node (ref "IC10") (pin "12") (pinfunction "+IN_12") (pintype "input"))
      (node (ref "IC9") (pin "14") (pinfunction "OUT_14") (pintype "output"))
      (node (ref "Q6") (pin "2") (pinfunction "S_2") (pintype "passive"))
      (node (ref "R86") (pin "1") (pinfunction "1_1") (pintype "passive"))
      (node (ref "R94") (pin "1") (pinfunction "1_1") (pintype "passive"))
    )
    (net (code "123") (name "Net-(IC10D--IN)") (class "Default")
      (node (ref "IC10") (pin "13") (pinfunction "-IN_13") (pintype "input"))
      (node (ref "IC10") (pin "14") (pinfunction "OUT_14") (pintype "output"))
      (node (ref "R74") (pin "1") (pinfunction "1_1") (pintype "passive"))
    )
    (net (code "124") (name "Net-(IC11A--IN)") (class "Default")
      (node (ref "C7") (pin "1") (pinfunction "1_1") (pintype "passive"))
      (node (ref "IC11") (pin "2") (pinfunction "-IN_2") (pintype "input"))
      (node (ref "R80") (pin "1") (pinfunction "1_1") (pintype "passive"))
      (node (ref "T8") (pin "C") (pinfunction "C_C") (pintype "passive"))
    )
    (net (code "125") (name "Net-(IC11A-OUT)") (class "Default")
      (node (ref "C7") (pin "2") (pinfunction "2_2") (pintype "passive"))
      (node (ref "IC11") (pin "1") (pinfunction "OUT_1") (pintype "output"))
      (node (ref "R81") (pin "1") (pinfunction "1_1") (pintype "passive"))
    )
    (net (code "126") (name "Net-(IC11B--IN)") (class "Default")
      (node (ref "IC11") (pin "6") (pinfunction "-IN_6") (pintype "input"))
      (node (ref "R135") (pin "2") (pinfunction "2_2") (pintype "passive"))
      (node (ref "R77") (pin "2") (pinfunction "2_2") (pintype "passive"))
      (node (ref "R78") (pin "2") (pinfunction "2_2") (pintype "passive"))
      (node (ref "R79") (pin "1") (pinfunction "1_1") (pintype "passive"))
    )
    (net (code "127") (name "Net-(IC11B-OUT)") (class "Default")
      (node (ref "IC11") (pin "7") (pinfunction "OUT_7") (pintype "output"))
      (node (ref "R79") (pin "2") (pinfunction "2_2") (pintype "passive"))
      (node (ref "T8") (pin "B") (pinfunction "B_B") (pintype "passive"))
    )
    (net (code "128") (name "Net-(IC12A-+IN)") (class "Default")
      (node (ref "C17") (pin "1") (pinfunction "1_1") (pintype "passive"))
      (node (ref "IC12") (pin "3") (pinfunction "+IN_3") (pintype "input"))
      (node (ref "IC8") (pin "5") (pinfunction "OUT_5") (pintype "output"))
      (node (ref "R125") (pin "1") (pinfunction "1_1") (pintype "passive"))
    )
    (net (code "129") (name "Net-(IC12A-OUT)") (class "Default")
      (node (ref "C17") (pin "2") (pinfunction "2_2") (pintype "passive"))
      (node (ref "IC12") (pin "1") (pinfunction "OUT_1") (pintype "output"))
      (node (ref "R125") (pin "2") (pinfunction "2_2") (pintype "passive"))
      (node (ref "R126") (pin "2") (pinfunction "2_2") (pintype "passive"))
      (node (ref "R136") (pin "1") (pinfunction "1_1") (pintype "passive"))
      (node (ref "R138") (pin "2") (pinfunction "2_2") (pintype "passive"))
    )
    (net (code "130") (name "Net-(IC12B--IN)") (class "Default")
      (node (ref "IC12") (pin "6") (pinfunction "-IN_6") (pintype "input"))
      (node (ref "R138") (pin "1") (pinfunction "1_1") (pintype "passive"))
      (node (ref "R139") (pin "2") (pinfunction "2_2") (pintype "passive"))
    )
    (net (code "131") (name "Net-(IC12C-+IN)") (class "Default")
      (node (ref "C30") (pin "1") (pinfunction "1_1") (pintype "passive"))
      (node (ref "IC12") (pin "10") (pinfunction "+IN_10") (pintype "input"))
      (node (ref "R136") (pin "2") (pinfunction "2_2") (pintype "passive"))
      (node (ref "R137") (pin "1") (pinfunction "1_1") (pintype "passive"))
    )
    (net (code "132") (name "Net-(IC12C-OUT)") (class "Default")
      (node (ref "C30") (pin "2") (pinfunction "2_2") (pintype "passive"))
      (node (ref "D9") (pin "A") (pinfunction "A_A") (pintype "passive"))
      (node (ref "IC12") (pin "8") (pinfunction "OUT_8") (pintype "output"))
      (node (ref "IC8") (pin "7") (pinfunction "B_7") (pintype "passive"))
      (node (ref "R137") (pin "2") (pinfunction "2_2") (pintype "passive"))
    )
    (net (code "133") (name "Net-(IC12D--IN)") (class "Default")
      (node (ref "C16") (pin "1") (pinfunction "1_1") (pintype "passive"))
      (node (ref "IC12") (pin "13") (pinfunction "-IN_13") (pintype "input"))
      (node (ref "R117") (pin "2") (pinfunction "2_2") (pintype "passive"))
      (node (ref "R118") (pin "2") (pinfunction "2_2") (pintype "passive"))
      (node (ref "R121") (pin "1") (pinfunction "1_1") (pintype "passive"))
      (node (ref "R140") (pin "2") (pinfunction "2_2") (pintype "passive"))
    )
    (net (code "134") (name "Net-(IC12D-OUT)") (class "Default")
      (node (ref "C16") (pin "2") (pinfunction "2_2") (pintype "passive"))
      (node (ref "IC12") (pin "14") (pinfunction "OUT_14") (pintype "output"))
      (node (ref "R116") (pin "1") (pinfunction "1_1") (pintype "passive"))
    )
    (net (code "135") (name "Net-(Q1-D)") (class "Default")
      (node (ref "Q1") (pin "1") (pinfunction "D_1") (pintype "passive"))
      (node (ref "R61") (pin "1") (pinfunction "1_1") (pintype "passive"))
    )
    (net (code "136") (name "Net-(Q1-G)") (class "Default")
      (node (ref "Q1") (pin "3") (pinfunction "G_3") (pintype "passive"))
      (node (ref "R59") (pin "2") (pinfunction "2_2") (pintype "passive"))
    )
    (net (code "137") (name "Net-(Q2-D)") (class "Default")
      (node (ref "Q2") (pin "1") (pinfunction "D_1") (pintype "passive"))
      (node (ref "R65") (pin "2") (pinfunction "2_2") (pintype "passive"))
    )
    (net (code "138") (name "Net-(Q2-G)") (class "Default")
      (node (ref "Q2") (pin "3") (pinfunction "G_3") (pintype "passive"))
      (node (ref "R58") (pin "2") (pinfunction "2_2") (pintype "passive"))
    )
    (net (code "139") (name "Net-(Q3-D)") (class "Default")
      (node (ref "Q3") (pin "1") (pinfunction "D_1") (pintype "passive"))
      (node (ref "R99") (pin "1") (pinfunction "1_1") (pintype "passive"))
    )
    (net (code "140") (name "Net-(Q3-G)") (class "Default")
      (node (ref "Q3") (pin "3") (pinfunction "G_3") (pintype "passive"))
      (node (ref "R97") (pin "2") (pinfunction "2_2") (pintype "passive"))
    )
    (net (code "141") (name "Net-(Q4-D)") (class "Default")
      (node (ref "Q4") (pin "1") (pinfunction "D_1") (pintype "passive"))
      (node (ref "R23") (pin "1") (pinfunction "1_1") (pintype "passive"))
    )
    (net (code "142") (name "Net-(Q4-G)") (class "Default")
      (node (ref "Q4") (pin "3") (pinfunction "G_3") (pintype "passive"))
      (node (ref "R21") (pin "2") (pinfunction "2_2") (pintype "passive"))
    )
    (net (code "143") (name "Net-(Q5-D)") (class "Default")
      (node (ref "Q5") (pin "1") (pinfunction "D_1") (pintype "passive"))
      (node (ref "R27") (pin "2") (pinfunction "2_2") (pintype "passive"))
    )
    (net (code "144") (name "Net-(Q5-G)") (class "Default")
      (node (ref "Q5") (pin "3") (pinfunction "G_3") (pintype "passive"))
      (node (ref "R20") (pin "2") (pinfunction "2_2") (pintype "passive"))
    )
    (net (code "145") (name "Net-(Q6-D)") (class "Default")
      (node (ref "Q6") (pin "1") (pinfunction "D_1") (pintype "passive"))
      (node (ref "R103") (pin "2") (pinfunction "2_2") (pintype "passive"))
    )
    (net (code "146") (name "Net-(Q6-G)") (class "Default")
      (node (ref "Q6") (pin "3") (pinfunction "G_3") (pintype "passive"))
      (node (ref "R96") (pin "2") (pinfunction "2_2") (pintype "passive"))
    )
    (net (code "147") (name "Net-(R5-Pad2)") (class "Default")
      (node (ref "R5") (pin "2") (pinfunction "2_2") (pintype "passive"))
      (node (ref "T2") (pin "E") (pinfunction "E_E") (pintype "passive"))
      (node (ref "T3") (pin "E") (pinfunction "E_E") (pintype "passive"))
    )
    (net (code "148") (name "Net-(R6-Pad2)") (class "Default")
      (node (ref "R6") (pin "2") (pinfunction "2_2") (pintype "passive"))
      (node (ref "T1") (pin "E") (pinfunction "E_E") (pintype "passive"))
    )
    (net (code "149") (name "Net-(R15-A)") (class "Default")
      (node (ref "R12") (pin "1") (pinfunction "1_1") (pintype "passive"))
      (node (ref "R15") (pin "3") (pinfunction "A_3") (pintype "passive"))
    )
    (net (code "150") (name "Net-(R15-E)") (class "Default")
      (node (ref "R13") (pin "1") (pinfunction "1_1") (pintype "passive"))
      (node (ref "R15") (pin "1") (pinfunction "E_1") (pintype "passive"))
    )
    (net (code "151") (name "Net-(R22-A)") (class "Default")
      (node (ref "R22") (pin "2") (pinfunction "S_2") (pintype "passive"))
      (node (ref "R22") (pin "3") (pinfunction "A_3") (pintype "passive"))
      (node (ref "R26") (pin "1") (pinfunction "1_1") (pintype "passive"))
    )
    (net (code "152") (name "Net-(R23-Pad2)") (class "Default")
      (node (ref "R23") (pin "2") (pinfunction "2_2") (pintype "passive"))
      (node (ref "R24") (pin "1") (pinfunction "1_1") (pintype "passive"))
      (node (ref "R25") (pin "2") (pinfunction "2_2") (pintype "passive"))
    )
    (net (code "153") (name "Net-(R26-Pad2)") (class "Default")
      (node (ref "R26") (pin "2") (pinfunction "2_2") (pintype "passive"))
      (node (ref "R27") (pin "1") (pinfunction "1_1") (pintype "passive"))
      (node (ref "R28") (pin "1") (pinfunction "1_1") (pintype "passive"))
    )
    (net (code "154") (name "Net-(R43-Pad2)") (class "Default")
      (node (ref "R43") (pin "2") (pinfunction "2_2") (pintype "passive"))
      (node (ref "T5") (pin "E") (pinfunction "E_E") (pintype "passive"))
      (node (ref "T6") (pin "E") (pinfunction "E_E") (pintype "passive"))
    )
    (net (code "155") (name "Net-(R44-Pad2)") (class "Default")
      (node (ref "R44") (pin "2") (pinfunction "2_2") (pintype "passive"))
      (node (ref "T4") (pin "E") (pinfunction "E_E") (pintype "passive"))
    )
    (net (code "156") (name "Net-(R53-A)") (class "Default")
      (node (ref "R50") (pin "1") (pinfunction "1_1") (pintype "passive"))
      (node (ref "R53") (pin "3") (pinfunction "A_3") (pintype "passive"))
    )
    (net (code "157") (name "Net-(R53-E)") (class "Default")
      (node (ref "R51") (pin "1") (pinfunction "1_1") (pintype "passive"))
      (node (ref "R53") (pin "1") (pinfunction "E_1") (pintype "passive"))
    )
    (net (code "158") (name "Net-(R60-A)") (class "Default")
      (node (ref "R60") (pin "2") (pinfunction "S_2") (pintype "passive"))
      (node (ref "R60") (pin "3") (pinfunction "A_3") (pintype "passive"))
      (node (ref "R64") (pin "1") (pinfunction "1_1") (pintype "passive"))
    )
    (net (code "159") (name "Net-(R61-Pad2)") (class "Default")
      (node (ref "R61") (pin "2") (pinfunction "2_2") (pintype "passive"))
      (node (ref "R62") (pin "1") (pinfunction "1_1") (pintype "passive"))
      (node (ref "R63") (pin "2") (pinfunction "2_2") (pintype "passive"))
    )
    (net (code "160") (name "Net-(R64-Pad2)") (class "Default")
      (node (ref "R64") (pin "2") (pinfunction "2_2") (pintype "passive"))
      (node (ref "R65") (pin "1") (pinfunction "1_1") (pintype "passive"))
      (node (ref "R66") (pin "1") (pinfunction "1_1") (pintype "passive"))
    )
    (net (code "161") (name "Net-(R81-Pad2)") (class "Default")
      (node (ref "R81") (pin "2") (pinfunction "2_2") (pintype "passive"))
      (node (ref "T8") (pin "E") (pinfunction "E_E") (pintype "passive"))
      (node (ref "T9") (pin "E") (pinfunction "E_E") (pintype "passive"))
    )
    (net (code "162") (name "Net-(R82-Pad2)") (class "Default")
      (node (ref "R82") (pin "2") (pinfunction "2_2") (pintype "passive"))
      (node (ref "T7") (pin "E") (pinfunction "E_E") (pintype "passive"))
    )
    (net (code "163") (name "Net-(R91-A)") (class "Default")
      (node (ref "R88") (pin "1") (pinfunction "1_1") (pintype "passive"))
      (node (ref "R91") (pin "3") (pinfunction "A_3") (pintype "passive"))
    )
    (net (code "164") (name "Net-(R91-E)") (class "Default")
      (node (ref "R89") (pin "1") (pinfunction "1_1") (pintype "passive"))
      (node (ref "R91") (pin "1") (pinfunction "E_1") (pintype "passive"))
    )
    (net (code "165") (name "Net-(R98-A)") (class "Default")
      (node (ref "R102") (pin "1") (pinfunction "1_1") (pintype "passive"))
      (node (ref "R98") (pin "2") (pinfunction "S_2") (pintype "passive"))
      (node (ref "R98") (pin "3") (pinfunction "A_3") (pintype "passive"))
    )
    (net (code "166") (name "Net-(R100-Pad1)") (class "Default")
      (node (ref "R100") (pin "1") (pinfunction "1_1") (pintype "passive"))
      (node (ref "R101") (pin "2") (pinfunction "2_2") (pintype "passive"))
      (node (ref "R99") (pin "2") (pinfunction "2_2") (pintype "passive"))
    )
    (net (code "167") (name "Net-(R102-Pad2)") (class "Default")
      (node (ref "R102") (pin "2") (pinfunction "2_2") (pintype "passive"))
      (node (ref "R103") (pin "1") (pinfunction "1_1") (pintype "passive"))
      (node (ref "R104") (pin "1") (pinfunction "1_1") (pintype "passive"))
    )
    (net (code "168") (name "Net-(R116-Pad2)") (class "Default")
      (node (ref "R116") (pin "2") (pinfunction "2_2") (pintype "passive"))
      (node (ref "T10") (pin "B") (pinfunction "B_B") (pintype "passive"))
    )
    (net (code "169") (name "Net-(R118-Pad1)") (class "Default")
      (node (ref "R118") (pin "1") (pinfunction "1_1") (pintype "passive"))
      (node (ref "R119") (pin "2") (pinfunction "2_2") (pintype "passive"))
      (node (ref "R120") (pin "2") (pinfunction "2_2") (pintype "passive"))
    )
    (net (code "170") (name "Net-(R121-Pad2)") (class "Default")
      (node (ref "R121") (pin "2") (pinfunction "2_2") (pintype "passive"))
      (node (ref "T10") (pin "E") (pinfunction "E_E") (pintype "passive"))
    )
    (net (code "171") (name "Net-(T1-PadB)") (class "Default")
      (node (ref "T1") (pin "B") (pinfunction "B_B") (pintype "passive"))
      (node (ref "T3") (pin "C") (pinfunction "C_C") (pintype "passive"))
    )
    (net (code "172") (name "Net-(T4-PadB)") (class "Default")
      (node (ref "T4") (pin "B") (pinfunction "B_B") (pintype "passive"))
      (node (ref "T6") (pin "C") (pinfunction "C_C") (pintype "passive"))
    )
    (net (code "173") (name "Net-(T7-PadB)") (class "Default")
      (node (ref "T7") (pin "B") (pinfunction "B_B") (pintype "passive"))
      (node (ref "T9") (pin "C") (pinfunction "C_C") (pintype "passive"))
    )
    (net (code "174") (name "unconnected-(IC4C-I_DIODE-Pad2)") (class "Default")
      (node (ref "IC4") (pin "2") (pinfunction "I_DIODE_2") (pintype "input"))
    )
    (net (code "175") (name "unconnected-(IC4D-I_DIODE-Pad15)") (class "Default")
      (node (ref "IC4") (pin "15") (pinfunction "I_DIODE_15") (pintype "input"))
    )
    (net (code "176") (name "unconnected-(IC8C-I_DIODE-Pad2)") (class "Default")
      (node (ref "IC8") (pin "2") (pinfunction "I_DIODE_2") (pintype "input"))
    )
    (net (code "177") (name "unconnected-(IC8D-I_DIODE-Pad15)") (class "Default")
      (node (ref "IC8") (pin "15") (pinfunction "I_DIODE_15") (pintype "input"))
    )
    (net (code "178") (name "unconnected-(JP1-Pad1)") (class "Default")
      (node (ref "JP1") (pin "1") (pinfunction "1_1") (pintype "passive"))
    )
  )
)
